# SCH_R2.net
KiCad netlist of a schematic drawn in EasyEDA
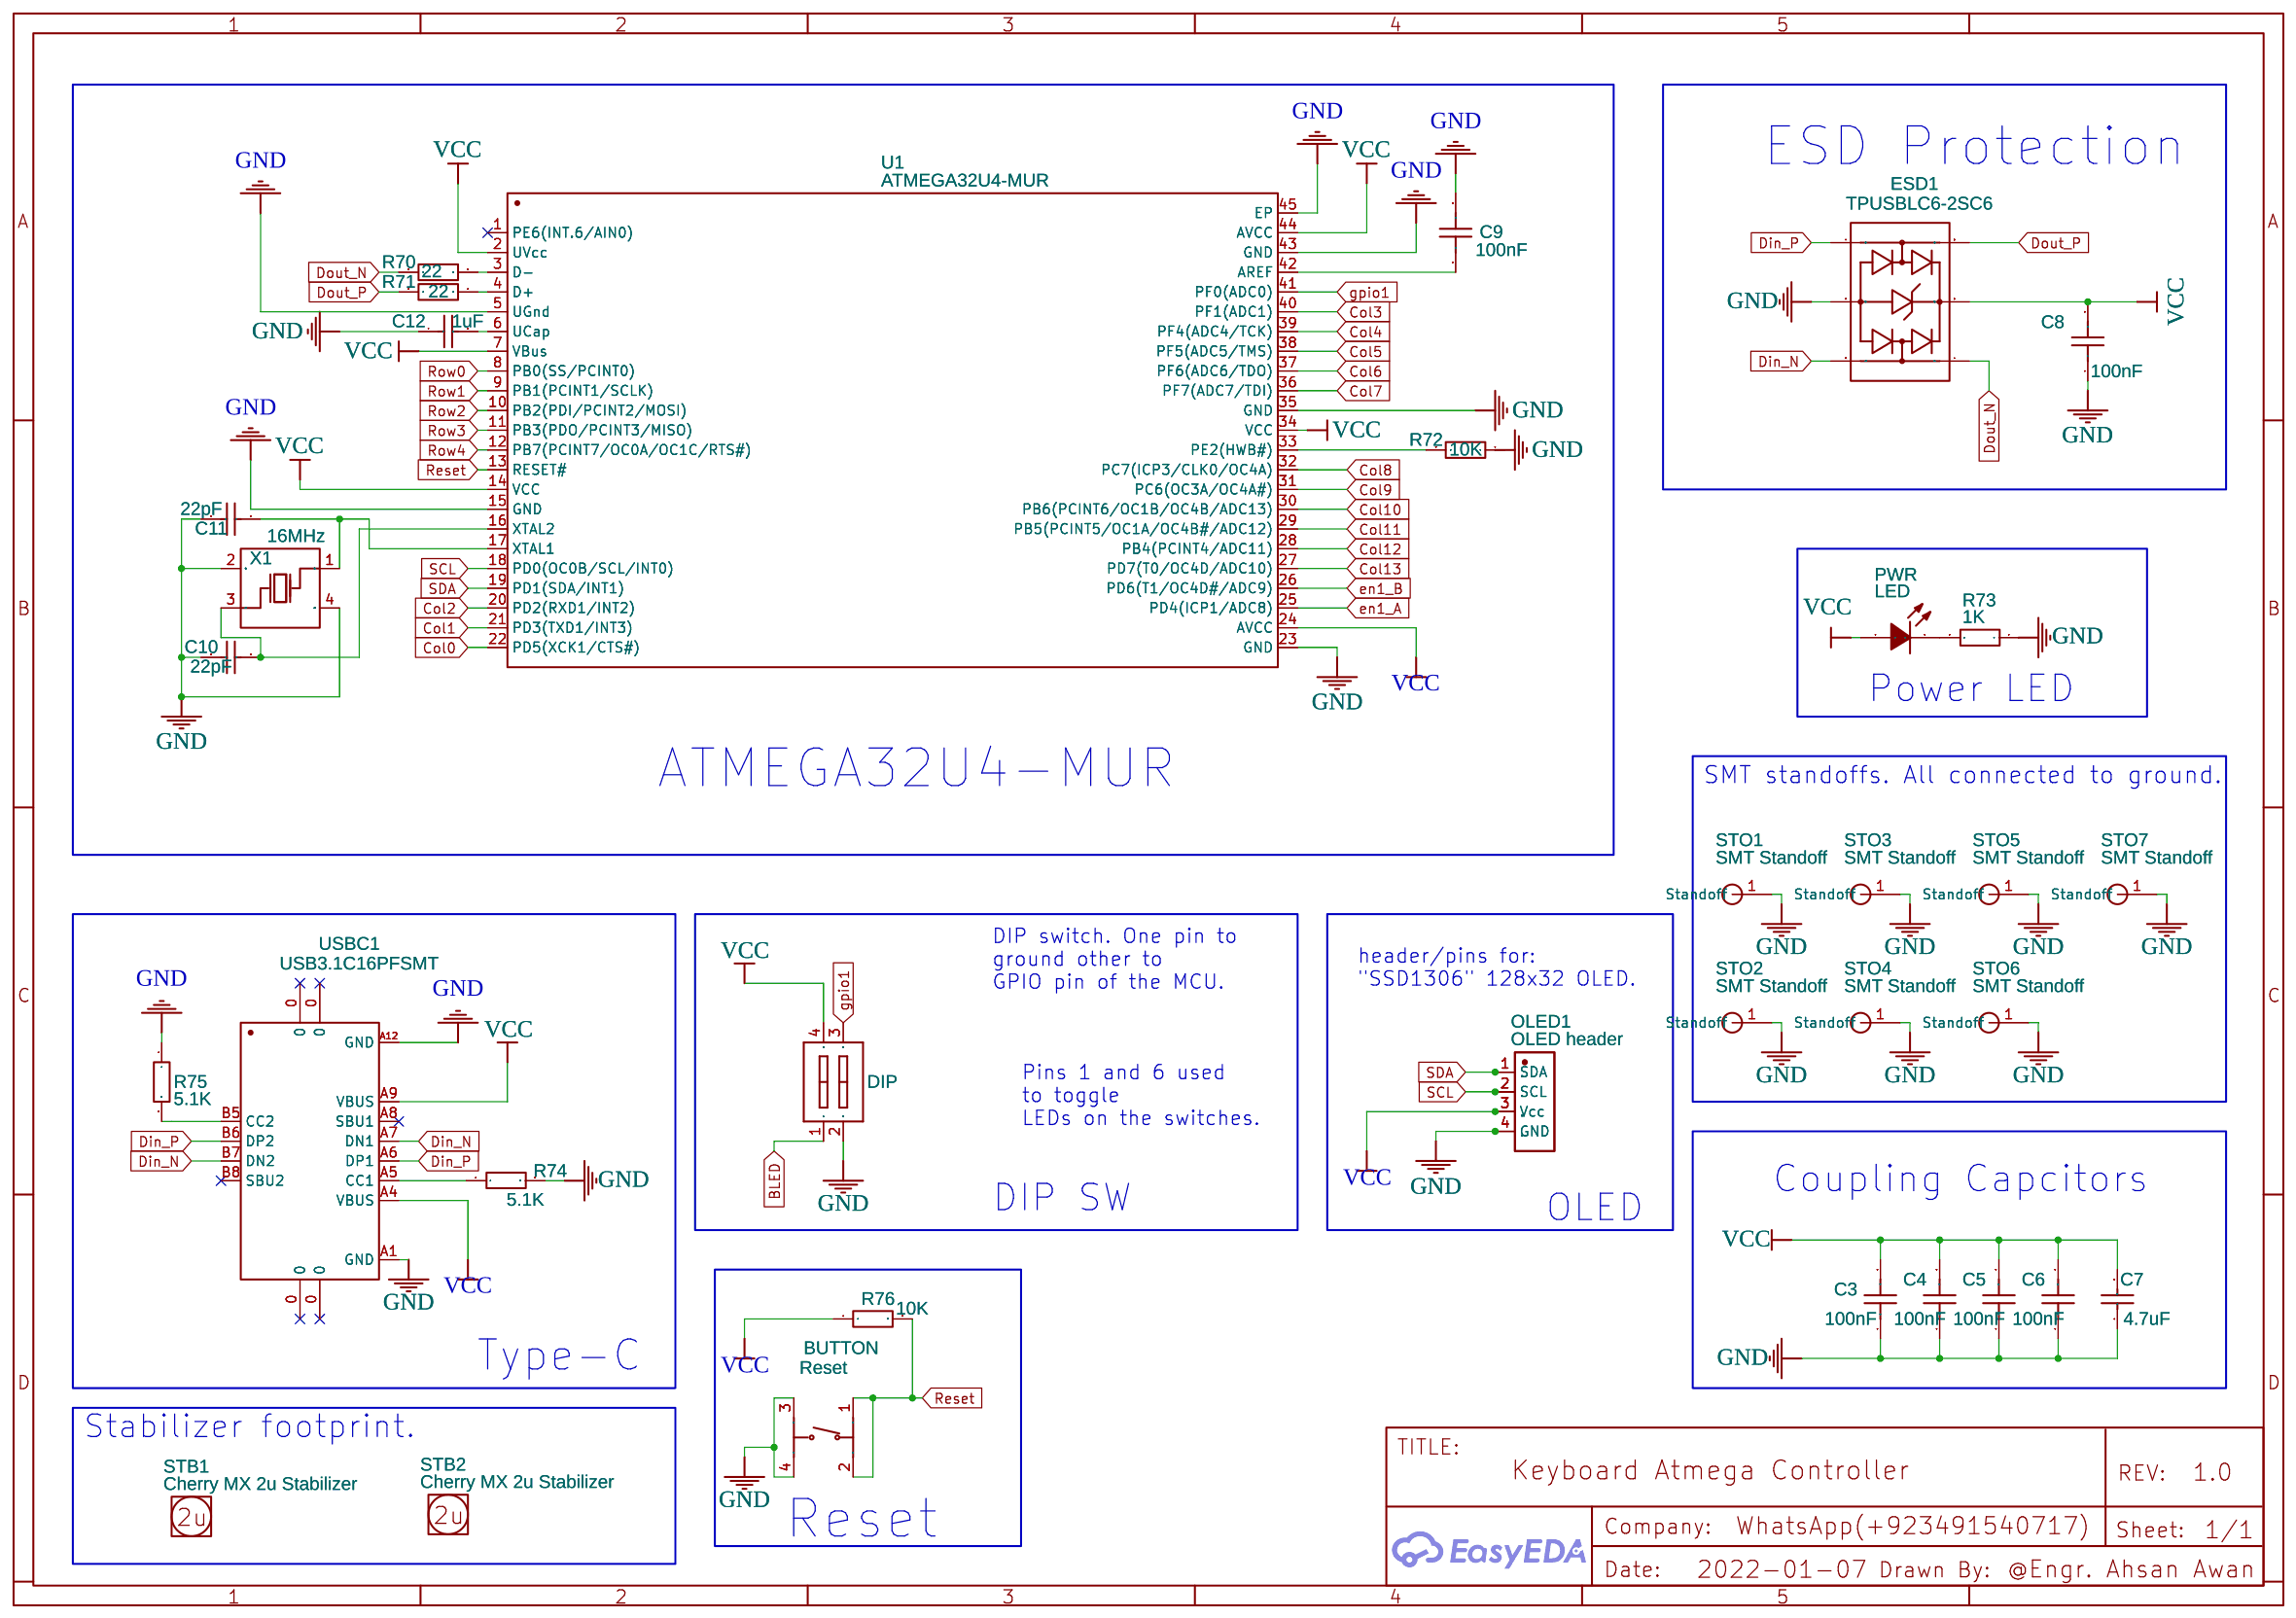
[diagram p0: Atmega MCU copy]
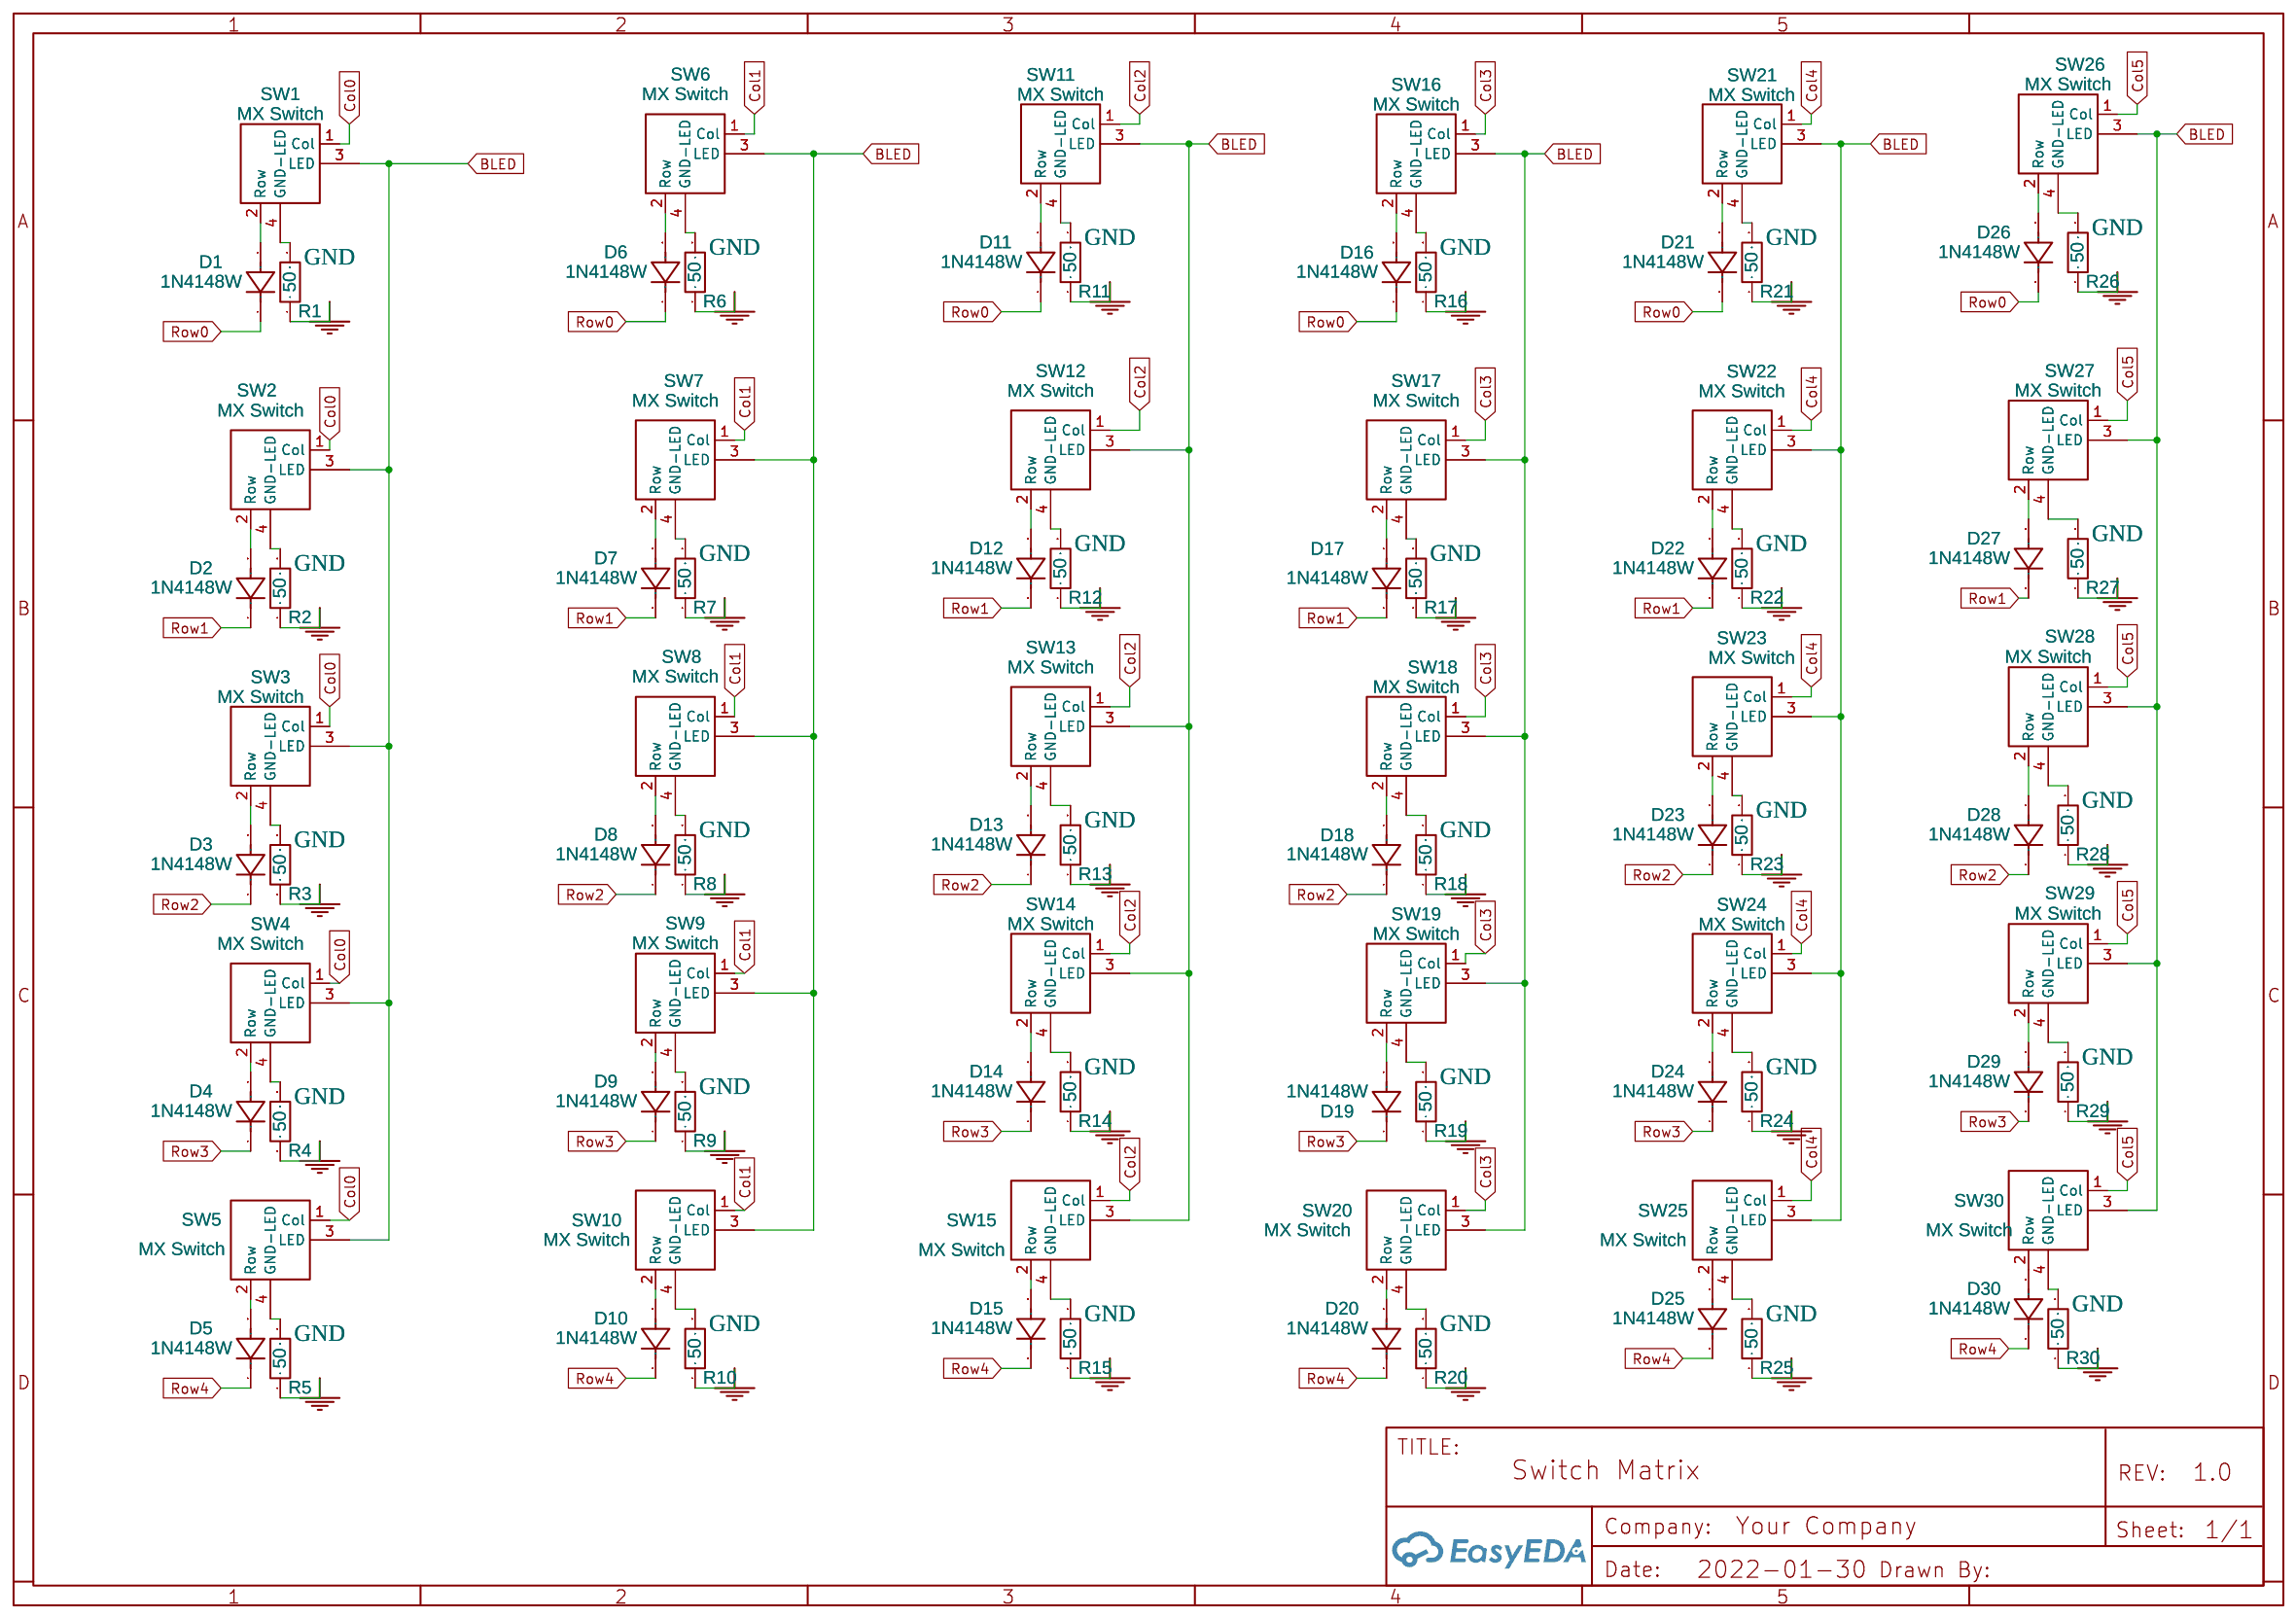
[diagram p1: First 6 Colimn]
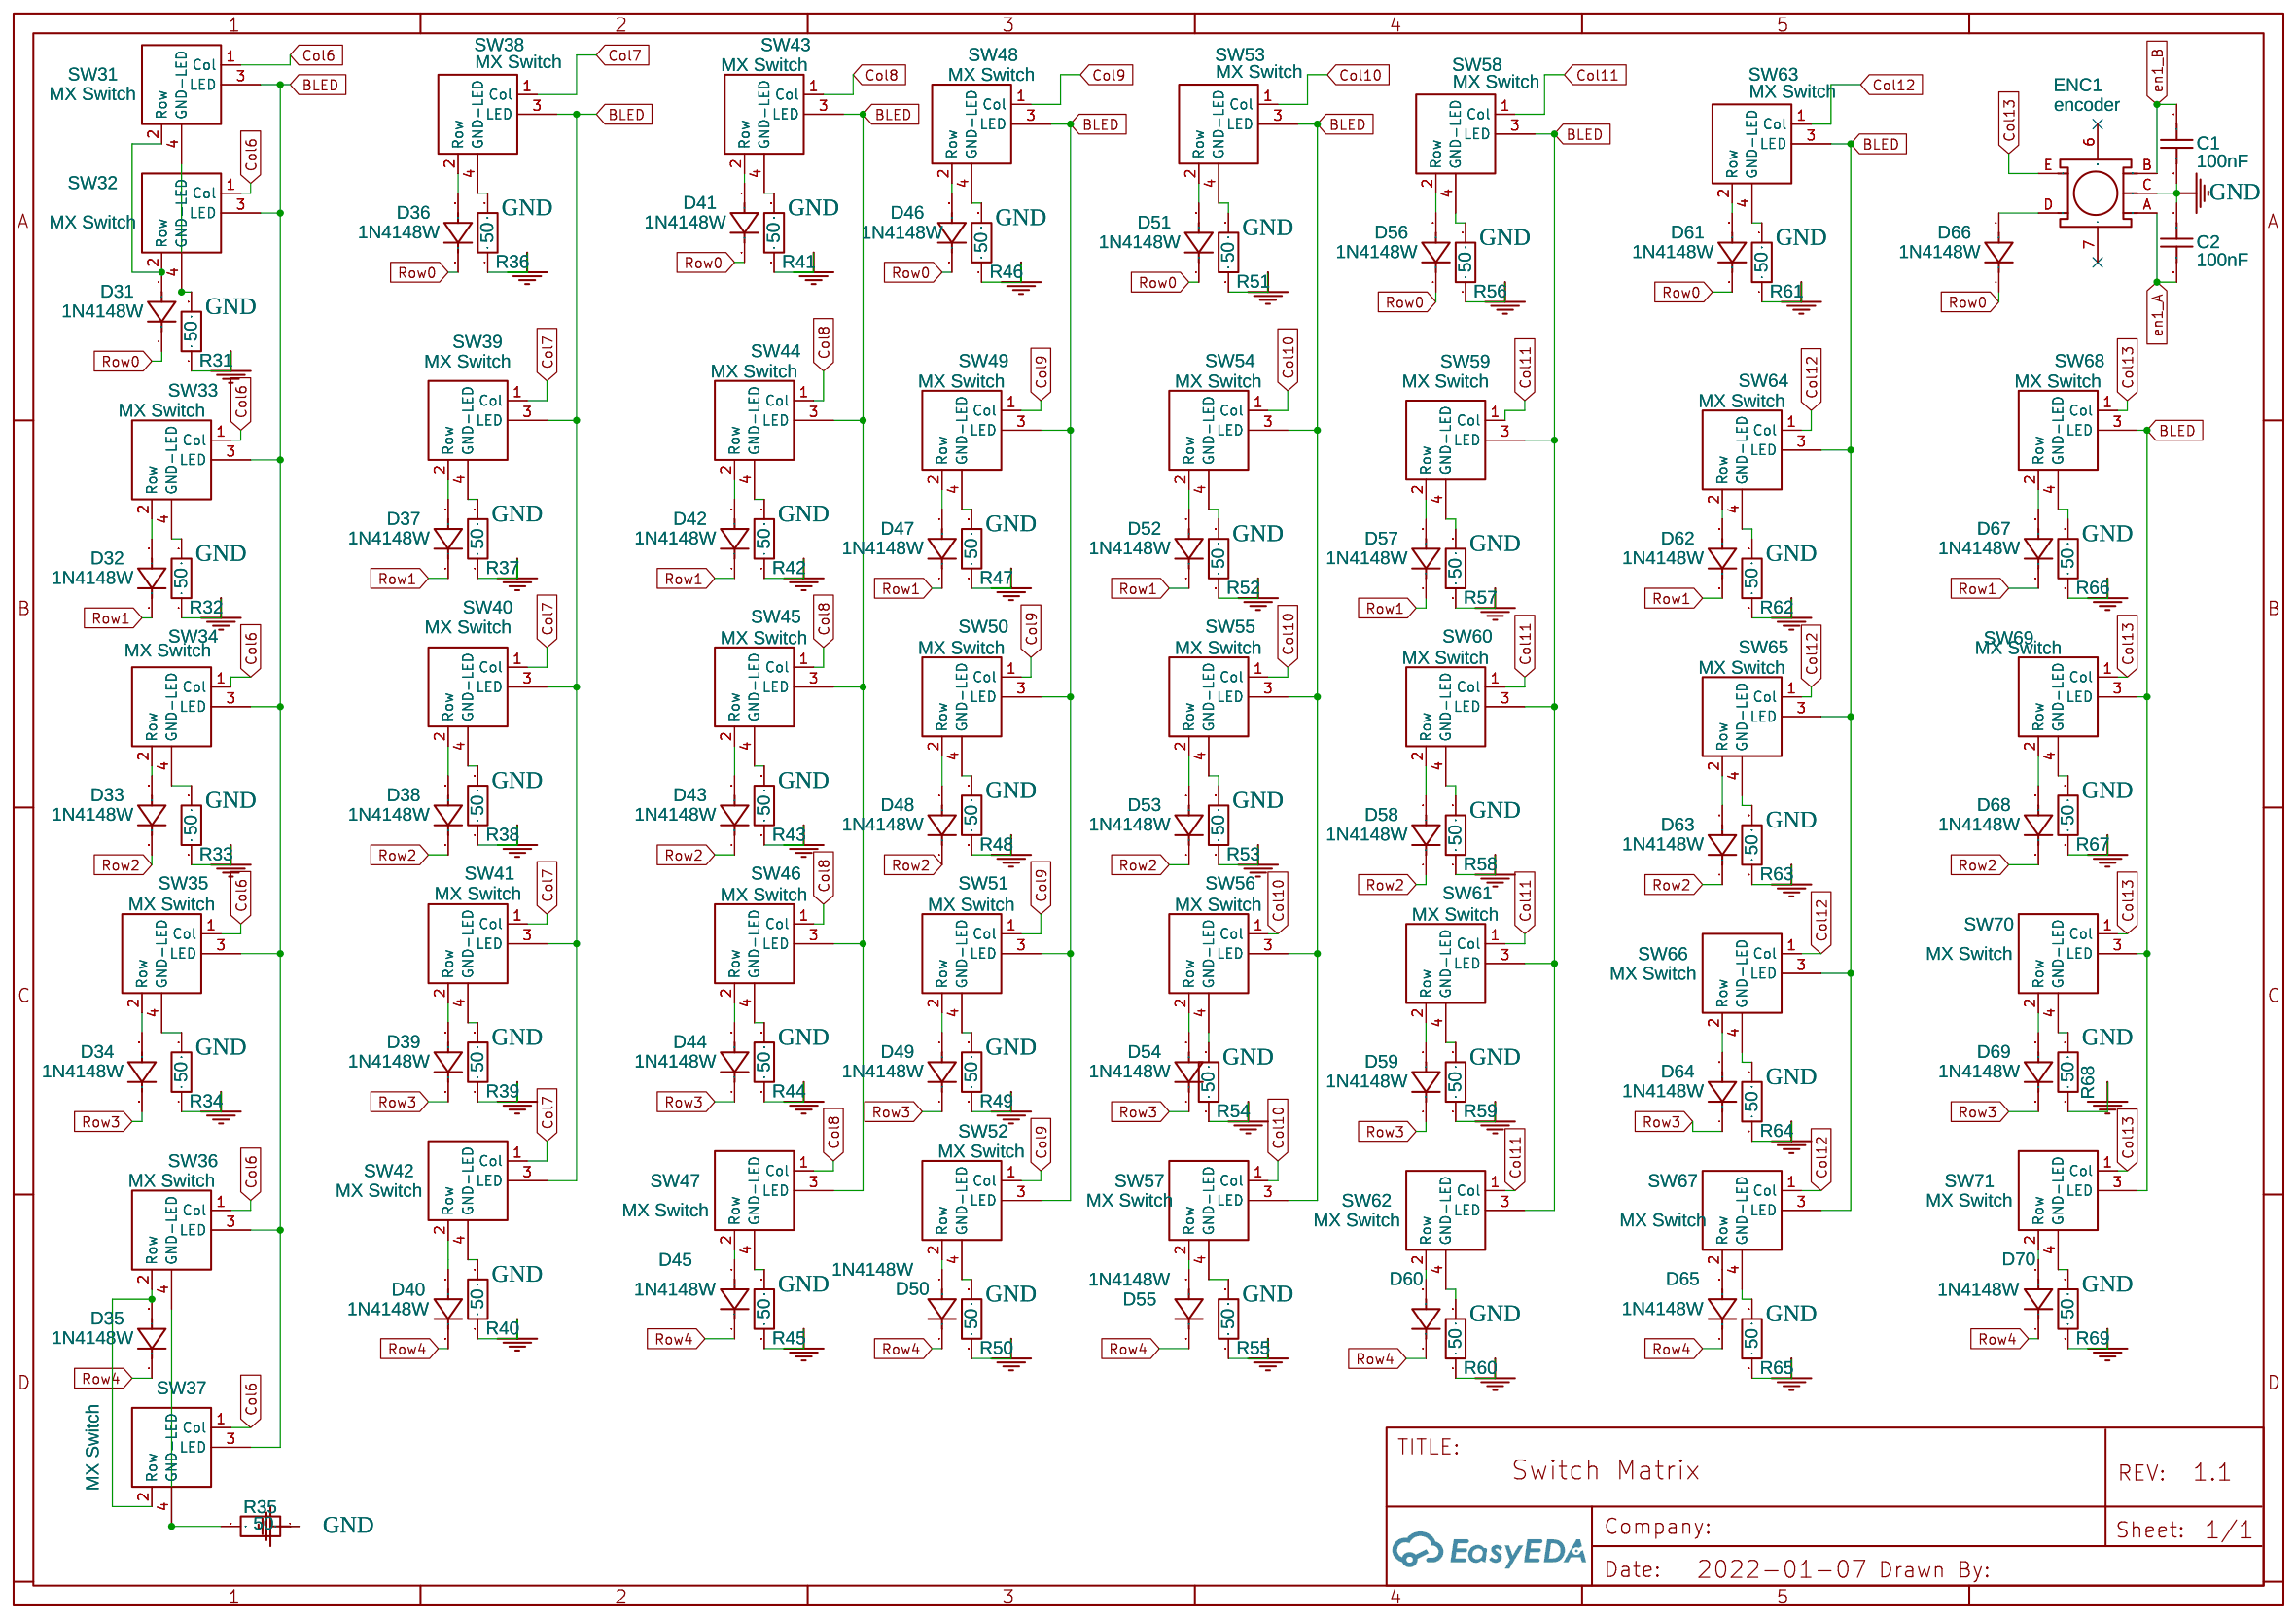
[diagram p2: Last 8 Col]

(export (version "E")
  (design (tool "Eeschema 10.0.6"))
  (components
    (comp (ref "BUTTON")
      (value "Reset")
      (fields
        (field (name "BOM_Manufacturer Part") "TS-1187A-B-A-B")
        (field (name "BOM_Supplier Part") "C318884")
      )
      (libsource (lib "") (part "TS-1187A-B-A-B"))
    )
    (comp (ref "C3")
      (value "100nF")
      (fields
        (field (name "BOM_Manufacturer Part") "CC0603KRX7R9BB104")
        (field (name "BOM_Supplier Part") "C14663")
      )
      (libsource (lib "") (part "CC0603KRX7R9BB104"))
    )
    (comp (ref "C4")
      (value "100nF")
      (fields
        (field (name "BOM_Manufacturer Part") "CC0603KRX7R9BB104")
        (field (name "BOM_Supplier Part") "C14663")
      )
      (libsource (lib "") (part "CC0603KRX7R9BB104"))
    )
    (comp (ref "C5")
      (value "100nF")
      (fields
        (field (name "BOM_Manufacturer Part") "CC0603KRX7R9BB104")
        (field (name "BOM_Supplier Part") "C14663")
      )
      (libsource (lib "") (part "CC0603KRX7R9BB104"))
    )
    (comp (ref "C6")
      (value "100nF")
      (fields
        (field (name "BOM_Manufacturer Part") "CC0603KRX7R9BB104")
        (field (name "BOM_Supplier Part") "C14663")
      )
      (libsource (lib "") (part "CC0603KRX7R9BB104"))
    )
    (comp (ref "C7")
      (value "4.7uF")
      (fields
        (field (name "BOM_Manufacturer Part") "CL10A475KO8NNNC")
        (field (name "BOM_Supplier Part") "C19666")
      )
      (libsource (lib "") (part "CL10A475KO8NNNC"))
    )
    (comp (ref "C8")
      (value "100nF")
      (fields
        (field (name "BOM_Manufacturer Part") "CC0603KRX7R9BB104")
        (field (name "BOM_Supplier Part") "C14663")
      )
      (libsource (lib "") (part "CC0603KRX7R9BB104"))
    )
    (comp (ref "C9")
      (value "100nF")
      (fields
        (field (name "BOM_Manufacturer Part") "CC0603KRX7R9BB104")
        (field (name "BOM_Supplier Part") "C14663")
      )
      (libsource (lib "") (part "CC0603KRX7R9BB104"))
    )
    (comp (ref "C10")
      (value "22pF")
      (fields
        (field (name "BOM_Manufacturer Part") "CL10C220JB8NNNC")
        (field (name "BOM_Supplier Part") "C1653")
      )
      (libsource (lib "") (part "CL10C220JB8NNNC"))
    )
    (comp (ref "C11")
      (value "22pF")
      (fields
        (field (name "BOM_Manufacturer Part") "CL10C220JB8NNNC")
        (field (name "BOM_Supplier Part") "C1653")
      )
      (libsource (lib "") (part "CL10C220JB8NNNC"))
    )
    (comp (ref "C12")
      (value "1uF")
      (fields
        (field (name "BOM_Manufacturer Part") "CL10A105KB8NNNC")
        (field (name "BOM_Supplier Part") "C15849")
      )
      (libsource (lib "") (part "CL10A105KB8NNNC"))
    )
    (comp (ref "DIP")
      (value "DSIC02LS-P_C489174")
      (fields
        (field (name "BOM_Manufacturer Part") "DSIC02LS-P")
        (field (name "BOM_Supplier Part") "C489174")
      )
      (libsource (lib "") (part "DSIC02LS-P_C489174"))
    )
    (comp (ref "ESD1")
      (value "TPUSBLC6-2SC6")
      (fields (field (name "BOM_Supplier Part") "C558442"))
      (libsource (lib "") (part "TPUSBLC6-2SC6"))
    )
    (comp (ref "OLED1")
      (value "OLED header")
      (fields
        (field (name "BOM_Manufacturer Part") "X4611WRS-04I-C40D28")
        (field (name "BOM_Supplier Part") "C917591")
      )
      (libsource (lib "") (part "X4611WRS-04I-C40D28"))
    )
    (comp (ref "PWR")
      (value "LED")
      (fields
        (field (name "BOM_Manufacturer Part") "TJ-S2012SW8TGLC6B-A5")
        (field (name "BOM_Supplier Part") "C192320")
      )
      (libsource (lib "") (part "TJ-S2012SW8TGLC6B-A5"))
    )
    (comp (ref "R70")
      (value "22")
      (fields
        (field (name "BOM_Manufacturer Part") "0603WAF220JT5E")
        (field (name "BOM_Supplier Part") "C23345")
      )
      (libsource (lib "") (part "0603WAF220JT5E"))
    )
    (comp (ref "R71")
      (value "22")
      (fields
        (field (name "BOM_Manufacturer Part") "0603WAF220JT5E")
        (field (name "BOM_Supplier Part") "C23345")
      )
      (libsource (lib "") (part "0603WAF220JT5E"))
    )
    (comp (ref "R72")
      (value "10K")
      (fields
        (field (name "BOM_Manufacturer Part") "0603WAF1002T5E")
        (field (name "BOM_Supplier Part") "C25804")
      )
      (libsource (lib "") (part "0603WAF1002T5E"))
    )
    (comp (ref "R73")
      (value "1K")
      (fields
        (field (name "BOM_Manufacturer Part") "TR0603B1KP0525")
        (field (name "BOM_Supplier Part") "C188364")
      )
      (libsource (lib "") (part "TR0603B1KP0525"))
    )
    (comp (ref "R74")
      (value "5.1K")
      (fields
        (field (name "BOM_Manufacturer Part") "RMC06035.1K1%N")
        (field (name "BOM_Supplier Part") "C269716")
      )
      (libsource (lib "") (part "RMC06035.1K1%N"))
    )
    (comp (ref "R75")
      (value "5.1K")
      (fields
        (field (name "BOM_Manufacturer Part") "RMC06035.1K1%N")
        (field (name "BOM_Supplier Part") "C269716")
      )
      (libsource (lib "") (part "RMC06035.1K1%N_1"))
    )
    (comp (ref "R76")
      (value "10K")
      (fields
        (field (name "BOM_Manufacturer Part") "0603WAF1002T5E")
        (field (name "BOM_Supplier Part") "C25804")
      )
      (libsource (lib "") (part "0603WAF1002T5E_1"))
    )
    (comp (ref "STB1")
      (value "Cherry MX 2u Stabilizer")
      (fields
        (field (name "BOM_Manufacturer Part") "G99-0742")
        (field (name "BOM_Supplier Part") "540-G99-0742")
      )
      (libsource (lib "") (part "Cherry MX 2u Stabilizer"))
    )
    (comp (ref "STB2")
      (value "Cherry MX 2u Stabilizer")
      (fields
        (field (name "BOM_Manufacturer Part") "G99-0742")
        (field (name "BOM_Supplier Part") "540-G99-0742")
      )
      (libsource (lib "") (part "Cherry MX 2u Stabilizer"))
    )
    (comp (ref "STO1")
      (value "SMT Standoff")
      (fields (field (name "BOM_Manufacturer Part") "9774040151R"))
      (libsource (lib "") (part "SMT Standoff"))
    )
    (comp (ref "STO2")
      (value "SMT Standoff")
      (fields (field (name "BOM_Manufacturer Part") "9774040151R"))
      (libsource (lib "") (part "SMT Standoff"))
    )
    (comp (ref "STO3")
      (value "SMT Standoff")
      (fields (field (name "BOM_Manufacturer Part") "9774040151R"))
      (libsource (lib "") (part "SMT Standoff"))
    )
    (comp (ref "STO4")
      (value "SMT Standoff")
      (fields (field (name "BOM_Manufacturer Part") "9774040151R"))
      (libsource (lib "") (part "SMT Standoff"))
    )
    (comp (ref "STO5")
      (value "SMT Standoff")
      (fields (field (name "BOM_Manufacturer Part") "9774040151R"))
      (libsource (lib "") (part "SMT Standoff"))
    )
    (comp (ref "STO6")
      (value "SMT Standoff")
      (fields (field (name "BOM_Manufacturer Part") "9774040151R"))
      (libsource (lib "") (part "SMT Standoff"))
    )
    (comp (ref "STO7")
      (value "SMT Standoff")
      (fields (field (name "BOM_Manufacturer Part") "9774040151R"))
      (libsource (lib "") (part "SMT Standoff"))
    )
    (comp (ref "U1")
      (value "ATMEGA32U4-MUR")
      (fields (field (name "BOM_Supplier Part") "C45874"))
      (libsource (lib "") (part "ATMEGA32U4-MUR"))
    )
    (comp (ref "U2")
      (value "x")
      (fields
        (field (name "BOM_Manufacturer Part") "PZ2.54-1X4P-ZW")
        (field (name "BOM_Supplier Part") "C2837836")
      )
      (libsource (lib "") (part "PZ2.54-1X4P-ZW"))
    )
    (comp (ref "USBC1")
      (value "USB3.1C16PFSMT")
      (fields (field (name "BOM_Supplier Part") "C167321"))
      (libsource (lib "") (part "USB3.1C16PFSMT"))
    )
    (comp (ref "X1")
      (value "16MHz")
      (fields
        (field (name "BOM_Manufacturer Part") "X322516MLB4SI")
        (field (name "BOM_Supplier Part") "C13738")
      )
      (libsource (lib "") (part "X322516MLB4SI"))
    )
    (comp (ref "D1")
      (value "1N4148W")
      (fields (field (name "BOM_Supplier Part") "C2828417"))
      (libsource (lib "") (part "1N4148W_C2828417"))
    )
    (comp (ref "D2")
      (value "1N4148W")
      (fields (field (name "BOM_Supplier Part") "C2828417"))
      (libsource (lib "") (part "1N4148W_C2828417"))
    )
    (comp (ref "D3")
      (value "1N4148W")
      (fields (field (name "BOM_Supplier Part") "C2828417"))
      (libsource (lib "") (part "1N4148W_C2828417"))
    )
    (comp (ref "D4")
      (value "1N4148W")
      (fields (field (name "BOM_Supplier Part") "C2828417"))
      (libsource (lib "") (part "1N4148W_C2828417"))
    )
    (comp (ref "D5")
      (value "1N4148W")
      (fields (field (name "BOM_Supplier Part") "C2828417"))
      (libsource (lib "") (part "1N4148W_C2828417"))
    )
    (comp (ref "D6")
      (value "1N4148W")
      (fields (field (name "BOM_Supplier Part") "C2828417"))
      (libsource (lib "") (part "1N4148W_C2828417"))
    )
    (comp (ref "D7")
      (value "1N4148W")
      (fields (field (name "BOM_Supplier Part") "C2828417"))
      (libsource (lib "") (part "1N4148W_C2828417"))
    )
    (comp (ref "D8")
      (value "1N4148W")
      (fields (field (name "BOM_Supplier Part") "C2828417"))
      (libsource (lib "") (part "1N4148W_C2828417"))
    )
    (comp (ref "D9")
      (value "1N4148W")
      (fields (field (name "BOM_Supplier Part") "C2828417"))
      (libsource (lib "") (part "1N4148W_C2828417"))
    )
    (comp (ref "D10")
      (value "1N4148W")
      (fields (field (name "BOM_Supplier Part") "C2828417"))
      (libsource (lib "") (part "1N4148W_C2828417"))
    )
    (comp (ref "D11")
      (value "1N4148W")
      (fields (field (name "BOM_Supplier Part") "C2828417"))
      (libsource (lib "") (part "1N4148W_C2828417"))
    )
    (comp (ref "D12")
      (value "1N4148W")
      (fields (field (name "BOM_Supplier Part") "C2828417"))
      (libsource (lib "") (part "1N4148W_C2828417"))
    )
    (comp (ref "D13")
      (value "1N4148W")
      (fields (field (name "BOM_Supplier Part") "C2828417"))
      (libsource (lib "") (part "1N4148W_C2828417"))
    )
    (comp (ref "D14")
      (value "1N4148W")
      (fields (field (name "BOM_Supplier Part") "C2828417"))
      (libsource (lib "") (part "1N4148W_C2828417"))
    )
    (comp (ref "D15")
      (value "1N4148W")
      (fields (field (name "BOM_Supplier Part") "C2828417"))
      (libsource (lib "") (part "1N4148W_C2828417"))
    )
    (comp (ref "D16")
      (value "1N4148W")
      (fields (field (name "BOM_Supplier Part") "C2828417"))
      (libsource (lib "") (part "1N4148W_C2828417"))
    )
    (comp (ref "D17")
      (value "1N4148W")
      (fields (field (name "BOM_Supplier Part") "C2828417"))
      (libsource (lib "") (part "1N4148W_C2828417"))
    )
    (comp (ref "D18")
      (value "1N4148W")
      (fields (field (name "BOM_Supplier Part") "C2828417"))
      (libsource (lib "") (part "1N4148W_C2828417"))
    )
    (comp (ref "D19")
      (value "1N4148W")
      (fields (field (name "BOM_Supplier Part") "C2828417"))
      (libsource (lib "") (part "1N4148W_C2828417"))
    )
    (comp (ref "D20")
      (value "1N4148W")
      (fields (field (name "BOM_Supplier Part") "C2828417"))
      (libsource (lib "") (part "1N4148W_C2828417"))
    )
    (comp (ref "D21")
      (value "1N4148W")
      (fields (field (name "BOM_Supplier Part") "C2828417"))
      (libsource (lib "") (part "1N4148W_C2828417"))
    )
    (comp (ref "D22")
      (value "1N4148W")
      (fields (field (name "BOM_Supplier Part") "C2828417"))
      (libsource (lib "") (part "1N4148W_C2828417"))
    )
    (comp (ref "D23")
      (value "1N4148W")
      (fields (field (name "BOM_Supplier Part") "C2828417"))
      (libsource (lib "") (part "1N4148W_C2828417"))
    )
    (comp (ref "D24")
      (value "1N4148W")
      (fields (field (name "BOM_Supplier Part") "C2828417"))
      (libsource (lib "") (part "1N4148W_C2828417"))
    )
    (comp (ref "D25")
      (value "1N4148W")
      (fields (field (name "BOM_Supplier Part") "C2828417"))
      (libsource (lib "") (part "1N4148W_C2828417"))
    )
    (comp (ref "D26")
      (value "1N4148W")
      (fields (field (name "BOM_Supplier Part") "C2828417"))
      (libsource (lib "") (part "1N4148W_C2828417"))
    )
    (comp (ref "D27")
      (value "1N4148W")
      (fields (field (name "BOM_Supplier Part") "C2828417"))
      (libsource (lib "") (part "1N4148W_C2828417"))
    )
    (comp (ref "D28")
      (value "1N4148W")
      (fields (field (name "BOM_Supplier Part") "C2828417"))
      (libsource (lib "") (part "1N4148W_C2828417"))
    )
    (comp (ref "D29")
      (value "1N4148W")
      (fields (field (name "BOM_Supplier Part") "C2828417"))
      (libsource (lib "") (part "1N4148W_C2828417"))
    )
    (comp (ref "D30")
      (value "1N4148W")
      (fields (field (name "BOM_Supplier Part") "C2828417"))
      (libsource (lib "") (part "1N4148W_C2828417"))
    )
    (comp (ref "R1")
      (value "50")
      (fields
        (field (name "BOM_Manufacturer Part") "HP03W5F500JT5E")
        (field (name "BOM_Supplier Part") "C2759402")
      )
      (libsource (lib "") (part "HP03W5F500JT5E"))
    )
    (comp (ref "R2")
      (value "50")
      (fields
        (field (name "BOM_Manufacturer Part") "HP03W5F500JT5E")
        (field (name "BOM_Supplier Part") "C2759402")
      )
      (libsource (lib "") (part "HP03W5F500JT5E"))
    )
    (comp (ref "R3")
      (value "50")
      (fields
        (field (name "BOM_Manufacturer Part") "HP03W5F500JT5E")
        (field (name "BOM_Supplier Part") "C2759402")
      )
      (libsource (lib "") (part "HP03W5F500JT5E"))
    )
    (comp (ref "R4")
      (value "50")
      (fields
        (field (name "BOM_Manufacturer Part") "HP03W5F500JT5E")
        (field (name "BOM_Supplier Part") "C2759402")
      )
      (libsource (lib "") (part "HP03W5F500JT5E"))
    )
    (comp (ref "R5")
      (value "50")
      (fields
        (field (name "BOM_Manufacturer Part") "HP03W5F500JT5E")
        (field (name "BOM_Supplier Part") "C2759402")
      )
      (libsource (lib "") (part "HP03W5F500JT5E"))
    )
    (comp (ref "R6")
      (value "50")
      (fields
        (field (name "BOM_Manufacturer Part") "HP03W5F500JT5E")
        (field (name "BOM_Supplier Part") "C2759402")
      )
      (libsource (lib "") (part "HP03W5F500JT5E"))
    )
    (comp (ref "R7")
      (value "50")
      (fields
        (field (name "BOM_Manufacturer Part") "HP03W5F500JT5E")
        (field (name "BOM_Supplier Part") "C2759402")
      )
      (libsource (lib "") (part "HP03W5F500JT5E"))
    )
    (comp (ref "R8")
      (value "50")
      (fields
        (field (name "BOM_Manufacturer Part") "HP03W5F500JT5E")
        (field (name "BOM_Supplier Part") "C2759402")
      )
      (libsource (lib "") (part "HP03W5F500JT5E"))
    )
    (comp (ref "R9")
      (value "50")
      (fields
        (field (name "BOM_Manufacturer Part") "HP03W5F500JT5E")
        (field (name "BOM_Supplier Part") "C2759402")
      )
      (libsource (lib "") (part "HP03W5F500JT5E"))
    )
    (comp (ref "R10")
      (value "50")
      (fields
        (field (name "BOM_Manufacturer Part") "HP03W5F500JT5E")
        (field (name "BOM_Supplier Part") "C2759402")
      )
      (libsource (lib "") (part "HP03W5F500JT5E"))
    )
    (comp (ref "R11")
      (value "50")
      (fields
        (field (name "BOM_Manufacturer Part") "HP03W5F500JT5E")
        (field (name "BOM_Supplier Part") "C2759402")
      )
      (libsource (lib "") (part "HP03W5F500JT5E"))
    )
    (comp (ref "R12")
      (value "50")
      (fields
        (field (name "BOM_Manufacturer Part") "HP03W5F500JT5E")
        (field (name "BOM_Supplier Part") "C2759402")
      )
      (libsource (lib "") (part "HP03W5F500JT5E"))
    )
    (comp (ref "R13")
      (value "50")
      (fields
        (field (name "BOM_Manufacturer Part") "HP03W5F500JT5E")
        (field (name "BOM_Supplier Part") "C2759402")
      )
      (libsource (lib "") (part "HP03W5F500JT5E"))
    )
    (comp (ref "R14")
      (value "50")
      (fields
        (field (name "BOM_Manufacturer Part") "HP03W5F500JT5E")
        (field (name "BOM_Supplier Part") "C2759402")
      )
      (libsource (lib "") (part "HP03W5F500JT5E"))
    )
    (comp (ref "R15")
      (value "50")
      (fields
        (field (name "BOM_Manufacturer Part") "HP03W5F500JT5E")
        (field (name "BOM_Supplier Part") "C2759402")
      )
      (libsource (lib "") (part "HP03W5F500JT5E"))
    )
    (comp (ref "R16")
      (value "50")
      (fields
        (field (name "BOM_Manufacturer Part") "HP03W5F500JT5E")
        (field (name "BOM_Supplier Part") "C2759402")
      )
      (libsource (lib "") (part "HP03W5F500JT5E"))
    )
    (comp (ref "R17")
      (value "50")
      (fields
        (field (name "BOM_Manufacturer Part") "HP03W5F500JT5E")
        (field (name "BOM_Supplier Part") "C2759402")
      )
      (libsource (lib "") (part "HP03W5F500JT5E"))
    )
    (comp (ref "R18")
      (value "50")
      (fields
        (field (name "BOM_Manufacturer Part") "HP03W5F500JT5E")
        (field (name "BOM_Supplier Part") "C2759402")
      )
      (libsource (lib "") (part "HP03W5F500JT5E"))
    )
    (comp (ref "R19")
      (value "50")
      (fields
        (field (name "BOM_Manufacturer Part") "HP03W5F500JT5E")
        (field (name "BOM_Supplier Part") "C2759402")
      )
      (libsource (lib "") (part "HP03W5F500JT5E"))
    )
    (comp (ref "R20")
      (value "50")
      (fields
        (field (name "BOM_Manufacturer Part") "HP03W5F500JT5E")
        (field (name "BOM_Supplier Part") "C2759402")
      )
      (libsource (lib "") (part "HP03W5F500JT5E"))
    )
    (comp (ref "R21")
      (value "50")
      (fields
        (field (name "BOM_Manufacturer Part") "HP03W5F500JT5E")
        (field (name "BOM_Supplier Part") "C2759402")
      )
      (libsource (lib "") (part "HP03W5F500JT5E"))
    )
    (comp (ref "R22")
      (value "50")
      (fields
        (field (name "BOM_Manufacturer Part") "HP03W5F500JT5E")
        (field (name "BOM_Supplier Part") "C2759402")
      )
      (libsource (lib "") (part "HP03W5F500JT5E"))
    )
    (comp (ref "R23")
      (value "50")
      (fields
        (field (name "BOM_Manufacturer Part") "HP03W5F500JT5E")
        (field (name "BOM_Supplier Part") "C2759402")
      )
      (libsource (lib "") (part "HP03W5F500JT5E"))
    )
    (comp (ref "R24")
      (value "50")
      (fields
        (field (name "BOM_Manufacturer Part") "HP03W5F500JT5E")
        (field (name "BOM_Supplier Part") "C2759402")
      )
      (libsource (lib "") (part "HP03W5F500JT5E"))
    )
    (comp (ref "R25")
      (value "50")
      (fields
        (field (name "BOM_Manufacturer Part") "HP03W5F500JT5E")
        (field (name "BOM_Supplier Part") "C2759402")
      )
      (libsource (lib "") (part "HP03W5F500JT5E"))
    )
    (comp (ref "R26")
      (value "50")
      (fields
        (field (name "BOM_Manufacturer Part") "HP03W5F500JT5E")
        (field (name "BOM_Supplier Part") "C2759402")
      )
      (libsource (lib "") (part "HP03W5F500JT5E"))
    )
    (comp (ref "R27")
      (value "50")
      (fields
        (field (name "BOM_Manufacturer Part") "HP03W5F500JT5E")
        (field (name "BOM_Supplier Part") "C2759402")
      )
      (libsource (lib "") (part "HP03W5F500JT5E"))
    )
    (comp (ref "R28")
      (value "50")
      (fields
        (field (name "BOM_Manufacturer Part") "HP03W5F500JT5E")
        (field (name "BOM_Supplier Part") "C2759402")
      )
      (libsource (lib "") (part "HP03W5F500JT5E"))
    )
    (comp (ref "R29")
      (value "50")
      (fields
        (field (name "BOM_Manufacturer Part") "HP03W5F500JT5E")
        (field (name "BOM_Supplier Part") "C2759402")
      )
      (libsource (lib "") (part "HP03W5F500JT5E"))
    )
    (comp (ref "R30")
      (value "50")
      (fields
        (field (name "BOM_Manufacturer Part") "HP03W5F500JT5E")
        (field (name "BOM_Supplier Part") "C2759402")
      )
      (libsource (lib "") (part "HP03W5F500JT5E"))
    )
    (comp (ref "SW1")
      (value "MX Switch")
      (fields (field (name "BOM_Supplier Part") "Cherry MX or Alps/Matias switch"))
      (libsource (lib "") (part "MX Switch"))
    )
    (comp (ref "SW2")
      (value "MX Switch")
      (fields (field (name "BOM_Supplier Part") "Cherry MX or Alps/Matias switch"))
      (libsource (lib "") (part "MX Switch"))
    )
    (comp (ref "SW3")
      (value "MX Switch")
      (fields (field (name "BOM_Supplier Part") "Cherry MX or Alps/Matias switch"))
      (libsource (lib "") (part "MX Switch"))
    )
    (comp (ref "SW4")
      (value "MX Switch")
      (fields (field (name "BOM_Supplier Part") "Cherry MX or Alps/Matias switch"))
      (libsource (lib "") (part "MX Switch"))
    )
    (comp (ref "SW5")
      (value "MX Switch")
      (fields (field (name "BOM_Supplier Part") "Cherry MX or Alps/Matias switch"))
      (libsource (lib "") (part "MX Switch"))
    )
    (comp (ref "SW6")
      (value "MX Switch")
      (fields (field (name "BOM_Supplier Part") "Cherry MX or Alps/Matias switch"))
      (libsource (lib "") (part "MX Switch"))
    )
    (comp (ref "SW7")
      (value "MX Switch")
      (fields (field (name "BOM_Supplier Part") "Cherry MX or Alps/Matias switch"))
      (libsource (lib "") (part "MX Switch"))
    )
    (comp (ref "SW8")
      (value "MX Switch")
      (fields (field (name "BOM_Supplier Part") "Cherry MX or Alps/Matias switch"))
      (libsource (lib "") (part "MX Switch"))
    )
    (comp (ref "SW9")
      (value "MX Switch")
      (fields (field (name "BOM_Supplier Part") "Cherry MX or Alps/Matias switch"))
      (libsource (lib "") (part "MX Switch"))
    )
    (comp (ref "SW10")
      (value "MX Switch")
      (fields (field (name "BOM_Supplier Part") "Cherry MX or Alps/Matias switch"))
      (libsource (lib "") (part "MX Switch"))
    )
    (comp (ref "SW11")
      (value "MX Switch")
      (fields (field (name "BOM_Supplier Part") "Cherry MX or Alps/Matias switch"))
      (libsource (lib "") (part "MX Switch"))
    )
    (comp (ref "SW12")
      (value "MX Switch")
      (fields (field (name "BOM_Supplier Part") "Cherry MX or Alps/Matias switch"))
      (libsource (lib "") (part "MX Switch"))
    )
    (comp (ref "SW13")
      (value "MX Switch")
      (fields (field (name "BOM_Supplier Part") "Cherry MX or Alps/Matias switch"))
      (libsource (lib "") (part "MX Switch"))
    )
    (comp (ref "SW14")
      (value "MX Switch")
      (fields (field (name "BOM_Supplier Part") "Cherry MX or Alps/Matias switch"))
      (libsource (lib "") (part "MX Switch"))
    )
    (comp (ref "SW15")
      (value "MX Switch")
      (fields (field (name "BOM_Supplier Part") "Cherry MX or Alps/Matias switch"))
      (libsource (lib "") (part "MX Switch"))
    )
    (comp (ref "SW16")
      (value "MX Switch")
      (fields (field (name "BOM_Supplier Part") "Cherry MX or Alps/Matias switch"))
      (libsource (lib "") (part "MX Switch"))
    )
    (comp (ref "SW17")
      (value "MX Switch")
      (fields (field (name "BOM_Supplier Part") "Cherry MX or Alps/Matias switch"))
      (libsource (lib "") (part "MX Switch"))
    )
    (comp (ref "SW18")
      (value "MX Switch")
      (fields (field (name "BOM_Supplier Part") "Cherry MX or Alps/Matias switch"))
      (libsource (lib "") (part "MX Switch"))
    )
    (comp (ref "SW19")
      (value "MX Switch")
      (fields (field (name "BOM_Supplier Part") "Cherry MX or Alps/Matias switch"))
      (libsource (lib "") (part "MX Switch"))
    )
    (comp (ref "SW20")
      (value "MX Switch")
      (fields (field (name "BOM_Supplier Part") "Cherry MX or Alps/Matias switch"))
      (libsource (lib "") (part "MX Switch"))
    )
    (comp (ref "SW21")
      (value "MX Switch")
      (fields (field (name "BOM_Supplier Part") "Cherry MX or Alps/Matias switch"))
      (libsource (lib "") (part "MX Switch"))
    )
    (comp (ref "SW22")
      (value "MX Switch")
      (fields (field (name "BOM_Supplier Part") "Cherry MX or Alps/Matias switch"))
      (libsource (lib "") (part "MX Switch"))
    )
    (comp (ref "SW23")
      (value "MX Switch")
      (fields (field (name "BOM_Supplier Part") "Cherry MX or Alps/Matias switch"))
      (libsource (lib "") (part "MX Switch"))
    )
    (comp (ref "SW24")
      (value "MX Switch")
      (fields (field (name "BOM_Supplier Part") "Cherry MX or Alps/Matias switch"))
      (libsource (lib "") (part "MX Switch"))
    )
    (comp (ref "SW25")
      (value "MX Switch")
      (fields (field (name "BOM_Supplier Part") "Cherry MX or Alps/Matias switch"))
      (libsource (lib "") (part "MX Switch"))
    )
    (comp (ref "SW26")
      (value "MX Switch")
      (fields (field (name "BOM_Supplier Part") "Cherry MX or Alps/Matias switch"))
      (libsource (lib "") (part "MX Switch"))
    )
    (comp (ref "SW27")
      (value "MX Switch")
      (fields (field (name "BOM_Supplier Part") "Cherry MX or Alps/Matias switch"))
      (libsource (lib "") (part "MX Switch"))
    )
    (comp (ref "SW28")
      (value "MX Switch")
      (fields (field (name "BOM_Supplier Part") "Cherry MX or Alps/Matias switch"))
      (libsource (lib "") (part "MX Switch"))
    )
    (comp (ref "SW29")
      (value "MX Switch")
      (fields (field (name "BOM_Supplier Part") "Cherry MX or Alps/Matias switch"))
      (libsource (lib "") (part "MX Switch"))
    )
    (comp (ref "SW30")
      (value "MX Switch")
      (fields (field (name "BOM_Supplier Part") "Cherry MX or Alps/Matias switch"))
      (libsource (lib "") (part "MX Switch"))
    )
    (comp (ref "C1")
      (value "100nF")
      (fields
        (field (name "BOM_Manufacturer Part") "CC0603KRX7R9BB104")
        (field (name "BOM_Supplier Part") "C14663")
      )
      (libsource (lib "") (part "CC0603KRX7R9BB104"))
    )
    (comp (ref "C2")
      (value "100nF")
      (fields
        (field (name "BOM_Manufacturer Part") "CC0603KRX7R9BB104")
        (field (name "BOM_Supplier Part") "C14663")
      )
      (libsource (lib "") (part "CC0603KRX7R9BB104"))
    )
    (comp (ref "D31")
      (value "1N4148W")
      (fields (field (name "BOM_Supplier Part") "C2828417"))
      (libsource (lib "") (part "1N4148W_C2828417"))
    )
    (comp (ref "D32")
      (value "1N4148W")
      (fields (field (name "BOM_Supplier Part") "C2828417"))
      (libsource (lib "") (part "1N4148W_C2828417"))
    )
    (comp (ref "D33")
      (value "1N4148W")
      (fields (field (name "BOM_Supplier Part") "C2828417"))
      (libsource (lib "") (part "1N4148W_C2828417"))
    )
    (comp (ref "D34")
      (value "1N4148W")
      (fields (field (name "BOM_Supplier Part") "C2828417"))
      (libsource (lib "") (part "1N4148W_C2828417"))
    )
    (comp (ref "D35")
      (value "1N4148W")
      (fields (field (name "BOM_Supplier Part") "C2828417"))
      (libsource (lib "") (part "1N4148W_C2828417"))
    )
    (comp (ref "D36")
      (value "1N4148W")
      (fields (field (name "BOM_Supplier Part") "C2828417"))
      (libsource (lib "") (part "1N4148W_C2828417"))
    )
    (comp (ref "D37")
      (value "1N4148W")
      (fields (field (name "BOM_Supplier Part") "C2828417"))
      (libsource (lib "") (part "1N4148W_C2828417"))
    )
    (comp (ref "D38")
      (value "1N4148W")
      (fields (field (name "BOM_Supplier Part") "C2828417"))
      (libsource (lib "") (part "1N4148W_C2828417"))
    )
    (comp (ref "D39")
      (value "1N4148W")
      (fields (field (name "BOM_Supplier Part") "C2828417"))
      (libsource (lib "") (part "1N4148W_C2828417"))
    )
    (comp (ref "D40")
      (value "1N4148W")
      (fields (field (name "BOM_Supplier Part") "C2828417"))
      (libsource (lib "") (part "1N4148W_C2828417"))
    )
    (comp (ref "D41")
      (value "1N4148W")
      (fields (field (name "BOM_Supplier Part") "C2828417"))
      (libsource (lib "") (part "1N4148W_C2828417"))
    )
    (comp (ref "D42")
      (value "1N4148W")
      (fields (field (name "BOM_Supplier Part") "C2828417"))
      (libsource (lib "") (part "1N4148W_C2828417"))
    )
    (comp (ref "D43")
      (value "1N4148W")
      (fields (field (name "BOM_Supplier Part") "C2828417"))
      (libsource (lib "") (part "1N4148W_C2828417"))
    )
    (comp (ref "D44")
      (value "1N4148W")
      (fields (field (name "BOM_Supplier Part") "C2828417"))
      (libsource (lib "") (part "1N4148W_C2828417"))
    )
    (comp (ref "D45")
      (value "1N4148W")
      (fields (field (name "BOM_Supplier Part") "C2828417"))
      (libsource (lib "") (part "1N4148W_C2828417"))
    )
    (comp (ref "D46")
      (value "1N4148W")
      (fields (field (name "BOM_Supplier Part") "C2828417"))
      (libsource (lib "") (part "1N4148W_C2828417"))
    )
    (comp (ref "D47")
      (value "1N4148W")
      (fields (field (name "BOM_Supplier Part") "C2828417"))
      (libsource (lib "") (part "1N4148W_C2828417"))
    )
    (comp (ref "D48")
      (value "1N4148W")
      (fields (field (name "BOM_Supplier Part") "C2828417"))
      (libsource (lib "") (part "1N4148W_C2828417"))
    )
    (comp (ref "D49")
      (value "1N4148W")
      (fields (field (name "BOM_Supplier Part") "C2828417"))
      (libsource (lib "") (part "1N4148W_C2828417"))
    )
    (comp (ref "D50")
      (value "1N4148W")
      (fields (field (name "BOM_Supplier Part") "C2828417"))
      (libsource (lib "") (part "1N4148W_C2828417"))
    )
    (comp (ref "D51")
      (value "1N4148W")
      (fields (field (name "BOM_Supplier Part") "C2828417"))
      (libsource (lib "") (part "1N4148W_C2828417"))
    )
    (comp (ref "D52")
      (value "1N4148W")
      (fields (field (name "BOM_Supplier Part") "C2828417"))
      (libsource (lib "") (part "1N4148W_C2828417"))
    )
    (comp (ref "D53")
      (value "1N4148W")
      (fields (field (name "BOM_Supplier Part") "C2828417"))
      (libsource (lib "") (part "1N4148W_C2828417"))
    )
    (comp (ref "D54")
      (value "1N4148W")
      (fields (field (name "BOM_Supplier Part") "C2828417"))
      (libsource (lib "") (part "1N4148W_C2828417"))
    )
    (comp (ref "D55")
      (value "1N4148W")
      (fields (field (name "BOM_Supplier Part") "C2828417"))
      (libsource (lib "") (part "1N4148W_C2828417"))
    )
    (comp (ref "D56")
      (value "1N4148W")
      (fields (field (name "BOM_Supplier Part") "C2828417"))
      (libsource (lib "") (part "1N4148W_C2828417"))
    )
    (comp (ref "D57")
      (value "1N4148W")
      (fields (field (name "BOM_Supplier Part") "C2828417"))
      (libsource (lib "") (part "1N4148W_C2828417"))
    )
    (comp (ref "D58")
      (value "1N4148W")
      (fields (field (name "BOM_Supplier Part") "C2828417"))
      (libsource (lib "") (part "1N4148W_C2828417"))
    )
    (comp (ref "D59")
      (value "1N4148W")
      (fields (field (name "BOM_Supplier Part") "C2828417"))
      (libsource (lib "") (part "1N4148W_C2828417"))
    )
    (comp (ref "D60")
      (value "1N4148W")
      (fields (field (name "BOM_Supplier Part") "C2828417"))
      (libsource (lib "") (part "1N4148W_C2828417"))
    )
    (comp (ref "D61")
      (value "1N4148W")
      (fields (field (name "BOM_Supplier Part") "C2828417"))
      (libsource (lib "") (part "1N4148W_C2828417"))
    )
    (comp (ref "D62")
      (value "1N4148W")
      (fields (field (name "BOM_Supplier Part") "C2828417"))
      (libsource (lib "") (part "1N4148W_C2828417"))
    )
    (comp (ref "D63")
      (value "1N4148W")
      (fields (field (name "BOM_Supplier Part") "C2828417"))
      (libsource (lib "") (part "1N4148W_C2828417"))
    )
    (comp (ref "D64")
      (value "1N4148W")
      (fields (field (name "BOM_Supplier Part") "C2828417"))
      (libsource (lib "") (part "1N4148W_C2828417"))
    )
    (comp (ref "D65")
      (value "1N4148W")
      (fields (field (name "BOM_Supplier Part") "C2828417"))
      (libsource (lib "") (part "1N4148W_C2828417"))
    )
    (comp (ref "D66")
      (value "1N4148W")
      (fields (field (name "BOM_Supplier Part") "C2828417"))
      (libsource (lib "") (part "1N4148W_C2828417"))
    )
    (comp (ref "D67")
      (value "1N4148W")
      (fields (field (name "BOM_Supplier Part") "C2828417"))
      (libsource (lib "") (part "1N4148W_C2828417"))
    )
    (comp (ref "D68")
      (value "1N4148W")
      (fields (field (name "BOM_Supplier Part") "C2828417"))
      (libsource (lib "") (part "1N4148W_C2828417"))
    )
    (comp (ref "D69")
      (value "1N4148W")
      (fields (field (name "BOM_Supplier Part") "C2828417"))
      (libsource (lib "") (part "1N4148W_C2828417"))
    )
    (comp (ref "D70")
      (value "1N4148W")
      (fields (field (name "BOM_Supplier Part") "C2828417"))
      (libsource (lib "") (part "1N4148W_C2828417"))
    )
    (comp (ref "ENC1")
      (value "encoder")
      (fields
        (field (name "BOM_Manufacturer Part") "EC11E18244AU")
        (field (name "BOM_Supplier Part") "C202365")
      )
      (libsource (lib "") (part "EC11E18244AU"))
    )
    (comp (ref "R31")
      (value "50")
      (fields
        (field (name "BOM_Manufacturer Part") "HP03W5F500JT5E")
        (field (name "BOM_Supplier Part") "C2759402")
      )
      (libsource (lib "") (part "HP03W5F500JT5E"))
    )
    (comp (ref "R32")
      (value "50")
      (fields
        (field (name "BOM_Manufacturer Part") "HP03W5F500JT5E")
        (field (name "BOM_Supplier Part") "C2759402")
      )
      (libsource (lib "") (part "HP03W5F500JT5E"))
    )
    (comp (ref "R33")
      (value "50")
      (fields
        (field (name "BOM_Manufacturer Part") "HP03W5F500JT5E")
        (field (name "BOM_Supplier Part") "C2759402")
      )
      (libsource (lib "") (part "HP03W5F500JT5E"))
    )
    (comp (ref "R34")
      (value "50")
      (fields
        (field (name "BOM_Manufacturer Part") "HP03W5F500JT5E")
        (field (name "BOM_Supplier Part") "C2759402")
      )
      (libsource (lib "") (part "HP03W5F500JT5E"))
    )
    (comp (ref "R35")
      (value "50")
      (fields
        (field (name "BOM_Manufacturer Part") "HP03W5F500JT5E")
        (field (name "BOM_Supplier Part") "C2759402")
      )
      (libsource (lib "") (part "HP03W5F500JT5E_1"))
    )
    (comp (ref "R36")
      (value "50")
      (fields
        (field (name "BOM_Manufacturer Part") "HP03W5F500JT5E")
        (field (name "BOM_Supplier Part") "C2759402")
      )
      (libsource (lib "") (part "HP03W5F500JT5E"))
    )
    (comp (ref "R37")
      (value "50")
      (fields
        (field (name "BOM_Manufacturer Part") "HP03W5F500JT5E")
        (field (name "BOM_Supplier Part") "C2759402")
      )
      (libsource (lib "") (part "HP03W5F500JT5E"))
    )
    (comp (ref "R38")
      (value "50")
      (fields
        (field (name "BOM_Manufacturer Part") "HP03W5F500JT5E")
        (field (name "BOM_Supplier Part") "C2759402")
      )
      (libsource (lib "") (part "HP03W5F500JT5E"))
    )
    (comp (ref "R39")
      (value "50")
      (fields
        (field (name "BOM_Manufacturer Part") "HP03W5F500JT5E")
        (field (name "BOM_Supplier Part") "C2759402")
      )
      (libsource (lib "") (part "HP03W5F500JT5E"))
    )
    (comp (ref "R40")
      (value "50")
      (fields
        (field (name "BOM_Manufacturer Part") "HP03W5F500JT5E")
        (field (name "BOM_Supplier Part") "C2759402")
      )
      (libsource (lib "") (part "HP03W5F500JT5E"))
    )
    (comp (ref "R41")
      (value "50")
      (fields
        (field (name "BOM_Manufacturer Part") "HP03W5F500JT5E")
        (field (name "BOM_Supplier Part") "C2759402")
      )
      (libsource (lib "") (part "HP03W5F500JT5E"))
    )
    (comp (ref "R42")
      (value "50")
      (fields
        (field (name "BOM_Manufacturer Part") "HP03W5F500JT5E")
        (field (name "BOM_Supplier Part") "C2759402")
      )
      (libsource (lib "") (part "HP03W5F500JT5E"))
    )
    (comp (ref "R43")
      (value "50")
      (fields
        (field (name "BOM_Manufacturer Part") "HP03W5F500JT5E")
        (field (name "BOM_Supplier Part") "C2759402")
      )
      (libsource (lib "") (part "HP03W5F500JT5E"))
    )
    (comp (ref "R44")
      (value "50")
      (fields
        (field (name "BOM_Manufacturer Part") "HP03W5F500JT5E")
        (field (name "BOM_Supplier Part") "C2759402")
      )
      (libsource (lib "") (part "HP03W5F500JT5E"))
    )
    (comp (ref "R45")
      (value "50")
      (fields
        (field (name "BOM_Manufacturer Part") "HP03W5F500JT5E")
        (field (name "BOM_Supplier Part") "C2759402")
      )
      (libsource (lib "") (part "HP03W5F500JT5E"))
    )
    (comp (ref "R46")
      (value "50")
      (fields
        (field (name "BOM_Manufacturer Part") "HP03W5F500JT5E")
        (field (name "BOM_Supplier Part") "C2759402")
      )
      (libsource (lib "") (part "HP03W5F500JT5E"))
    )
    (comp (ref "R47")
      (value "50")
      (fields
        (field (name "BOM_Manufacturer Part") "HP03W5F500JT5E")
        (field (name "BOM_Supplier Part") "C2759402")
      )
      (libsource (lib "") (part "HP03W5F500JT5E"))
    )
    (comp (ref "R48")
      (value "50")
      (fields
        (field (name "BOM_Manufacturer Part") "HP03W5F500JT5E")
        (field (name "BOM_Supplier Part") "C2759402")
      )
      (libsource (lib "") (part "HP03W5F500JT5E"))
    )
    (comp (ref "R49")
      (value "50")
      (fields
        (field (name "BOM_Manufacturer Part") "HP03W5F500JT5E")
        (field (name "BOM_Supplier Part") "C2759402")
      )
      (libsource (lib "") (part "HP03W5F500JT5E"))
    )
    (comp (ref "R50")
      (value "50")
      (fields
        (field (name "BOM_Manufacturer Part") "HP03W5F500JT5E")
        (field (name "BOM_Supplier Part") "C2759402")
      )
      (libsource (lib "") (part "HP03W5F500JT5E"))
    )
    (comp (ref "R51")
      (value "50")
      (fields
        (field (name "BOM_Manufacturer Part") "HP03W5F500JT5E")
        (field (name "BOM_Supplier Part") "C2759402")
      )
      (libsource (lib "") (part "HP03W5F500JT5E"))
    )
    (comp (ref "R52")
      (value "50")
      (fields
        (field (name "BOM_Manufacturer Part") "HP03W5F500JT5E")
        (field (name "BOM_Supplier Part") "C2759402")
      )
      (libsource (lib "") (part "HP03W5F500JT5E"))
    )
    (comp (ref "R53")
      (value "50")
      (fields
        (field (name "BOM_Manufacturer Part") "HP03W5F500JT5E")
        (field (name "BOM_Supplier Part") "C2759402")
      )
      (libsource (lib "") (part "HP03W5F500JT5E"))
    )
    (comp (ref "R54")
      (value "50")
      (fields
        (field (name "BOM_Manufacturer Part") "HP03W5F500JT5E")
        (field (name "BOM_Supplier Part") "C2759402")
      )
      (libsource (lib "") (part "HP03W5F500JT5E"))
    )
    (comp (ref "R55")
      (value "50")
      (fields
        (field (name "BOM_Manufacturer Part") "HP03W5F500JT5E")
        (field (name "BOM_Supplier Part") "C2759402")
      )
      (libsource (lib "") (part "HP03W5F500JT5E"))
    )
    (comp (ref "R56")
      (value "50")
      (fields
        (field (name "BOM_Manufacturer Part") "HP03W5F500JT5E")
        (field (name "BOM_Supplier Part") "C2759402")
      )
      (libsource (lib "") (part "HP03W5F500JT5E"))
    )
    (comp (ref "R57")
      (value "50")
      (fields
        (field (name "BOM_Manufacturer Part") "HP03W5F500JT5E")
        (field (name "BOM_Supplier Part") "C2759402")
      )
      (libsource (lib "") (part "HP03W5F500JT5E"))
    )
    (comp (ref "R58")
      (value "50")
      (fields
        (field (name "BOM_Manufacturer Part") "HP03W5F500JT5E")
        (field (name "BOM_Supplier Part") "C2759402")
      )
      (libsource (lib "") (part "HP03W5F500JT5E"))
    )
    (comp (ref "R59")
      (value "50")
      (fields
        (field (name "BOM_Manufacturer Part") "HP03W5F500JT5E")
        (field (name "BOM_Supplier Part") "C2759402")
      )
      (libsource (lib "") (part "HP03W5F500JT5E"))
    )
    (comp (ref "R60")
      (value "50")
      (fields
        (field (name "BOM_Manufacturer Part") "HP03W5F500JT5E")
        (field (name "BOM_Supplier Part") "C2759402")
      )
      (libsource (lib "") (part "HP03W5F500JT5E"))
    )
    (comp (ref "R61")
      (value "50")
      (fields
        (field (name "BOM_Manufacturer Part") "HP03W5F500JT5E")
        (field (name "BOM_Supplier Part") "C2759402")
      )
      (libsource (lib "") (part "HP03W5F500JT5E"))
    )
    (comp (ref "R62")
      (value "50")
      (fields
        (field (name "BOM_Manufacturer Part") "HP03W5F500JT5E")
        (field (name "BOM_Supplier Part") "C2759402")
      )
      (libsource (lib "") (part "HP03W5F500JT5E"))
    )
    (comp (ref "R63")
      (value "50")
      (fields
        (field (name "BOM_Manufacturer Part") "HP03W5F500JT5E")
        (field (name "BOM_Supplier Part") "C2759402")
      )
      (libsource (lib "") (part "HP03W5F500JT5E"))
    )
    (comp (ref "R64")
      (value "50")
      (fields
        (field (name "BOM_Manufacturer Part") "HP03W5F500JT5E")
        (field (name "BOM_Supplier Part") "C2759402")
      )
      (libsource (lib "") (part "HP03W5F500JT5E"))
    )
    (comp (ref "R65")
      (value "50")
      (fields
        (field (name "BOM_Manufacturer Part") "HP03W5F500JT5E")
        (field (name "BOM_Supplier Part") "C2759402")
      )
      (libsource (lib "") (part "HP03W5F500JT5E"))
    )
    (comp (ref "R66")
      (value "50")
      (fields
        (field (name "BOM_Manufacturer Part") "HP03W5F500JT5E")
        (field (name "BOM_Supplier Part") "C2759402")
      )
      (libsource (lib "") (part "HP03W5F500JT5E"))
    )
    (comp (ref "R67")
      (value "50")
      (fields
        (field (name "BOM_Manufacturer Part") "HP03W5F500JT5E")
        (field (name "BOM_Supplier Part") "C2759402")
      )
      (libsource (lib "") (part "HP03W5F500JT5E"))
    )
    (comp (ref "R68")
      (value "50")
      (fields
        (field (name "BOM_Manufacturer Part") "HP03W5F500JT5E")
        (field (name "BOM_Supplier Part") "C2759402")
      )
      (libsource (lib "") (part "HP03W5F500JT5E"))
    )
    (comp (ref "R69")
      (value "50")
      (fields
        (field (name "BOM_Manufacturer Part") "HP03W5F500JT5E")
        (field (name "BOM_Supplier Part") "C2759402")
      )
      (libsource (lib "") (part "HP03W5F500JT5E"))
    )
    (comp (ref "SW31")
      (value "MX Switch")
      (fields (field (name "BOM_Supplier Part") "Cherry MX or Alps/Matias switch"))
      (libsource (lib "") (part "MX Switch"))
    )
    (comp (ref "SW32")
      (value "MX Switch")
      (fields (field (name "BOM_Supplier Part") "Cherry MX or Alps/Matias switch"))
      (libsource (lib "") (part "MX Switch"))
    )
    (comp (ref "SW33")
      (value "MX Switch")
      (fields (field (name "BOM_Supplier Part") "Cherry MX or Alps/Matias switch"))
      (libsource (lib "") (part "MX Switch"))
    )
    (comp (ref "SW34")
      (value "MX Switch")
      (fields (field (name "BOM_Supplier Part") "Cherry MX or Alps/Matias switch"))
      (libsource (lib "") (part "MX Switch"))
    )
    (comp (ref "SW35")
      (value "MX Switch")
      (fields (field (name "BOM_Supplier Part") "Cherry MX or Alps/Matias switch"))
      (libsource (lib "") (part "MX Switch"))
    )
    (comp (ref "SW36")
      (value "MX Switch")
      (fields (field (name "BOM_Supplier Part") "Cherry MX or Alps/Matias switch"))
      (libsource (lib "") (part "MX Switch"))
    )
    (comp (ref "SW37")
      (value "MX Switch")
      (fields (field (name "BOM_Supplier Part") "Cherry MX or Alps/Matias switch"))
      (libsource (lib "") (part "MX Switch"))
    )
    (comp (ref "SW38")
      (value "MX Switch")
      (fields (field (name "BOM_Supplier Part") "Cherry MX or Alps/Matias switch"))
      (libsource (lib "") (part "MX Switch"))
    )
    (comp (ref "SW39")
      (value "MX Switch")
      (fields (field (name "BOM_Supplier Part") "Cherry MX or Alps/Matias switch"))
      (libsource (lib "") (part "MX Switch"))
    )
    (comp (ref "SW40")
      (value "MX Switch")
      (fields (field (name "BOM_Supplier Part") "Cherry MX or Alps/Matias switch"))
      (libsource (lib "") (part "MX Switch"))
    )
    (comp (ref "SW41")
      (value "MX Switch")
      (fields (field (name "BOM_Supplier Part") "Cherry MX or Alps/Matias switch"))
      (libsource (lib "") (part "MX Switch"))
    )
    (comp (ref "SW42")
      (value "MX Switch")
      (fields (field (name "BOM_Supplier Part") "Cherry MX or Alps/Matias switch"))
      (libsource (lib "") (part "MX Switch"))
    )
    (comp (ref "SW43")
      (value "MX Switch")
      (fields (field (name "BOM_Supplier Part") "Cherry MX or Alps/Matias switch"))
      (libsource (lib "") (part "MX Switch"))
    )
    (comp (ref "SW44")
      (value "MX Switch")
      (fields (field (name "BOM_Supplier Part") "Cherry MX or Alps/Matias switch"))
      (libsource (lib "") (part "MX Switch"))
    )
    (comp (ref "SW45")
      (value "MX Switch")
      (fields (field (name "BOM_Supplier Part") "Cherry MX or Alps/Matias switch"))
      (libsource (lib "") (part "MX Switch"))
    )
    (comp (ref "SW46")
      (value "MX Switch")
      (fields (field (name "BOM_Supplier Part") "Cherry MX or Alps/Matias switch"))
      (libsource (lib "") (part "MX Switch"))
    )
    (comp (ref "SW47")
      (value "MX Switch")
      (fields (field (name "BOM_Supplier Part") "Cherry MX or Alps/Matias switch"))
      (libsource (lib "") (part "MX Switch"))
    )
    (comp (ref "SW48")
      (value "MX Switch")
      (fields (field (name "BOM_Supplier Part") "Cherry MX or Alps/Matias switch"))
      (libsource (lib "") (part "MX Switch"))
    )
    (comp (ref "SW49")
      (value "MX Switch")
      (fields (field (name "BOM_Supplier Part") "Cherry MX or Alps/Matias switch"))
      (libsource (lib "") (part "MX Switch"))
    )
    (comp (ref "SW50")
      (value "MX Switch")
      (fields (field (name "BOM_Supplier Part") "Cherry MX or Alps/Matias switch"))
      (libsource (lib "") (part "MX Switch"))
    )
    (comp (ref "SW51")
      (value "MX Switch")
      (fields (field (name "BOM_Supplier Part") "Cherry MX or Alps/Matias switch"))
      (libsource (lib "") (part "MX Switch"))
    )
    (comp (ref "SW52")
      (value "MX Switch")
      (fields (field (name "BOM_Supplier Part") "Cherry MX or Alps/Matias switch"))
      (libsource (lib "") (part "MX Switch"))
    )
    (comp (ref "SW53")
      (value "MX Switch")
      (fields (field (name "BOM_Supplier Part") "Cherry MX or Alps/Matias switch"))
      (libsource (lib "") (part "MX Switch"))
    )
    (comp (ref "SW54")
      (value "MX Switch")
      (fields (field (name "BOM_Supplier Part") "Cherry MX or Alps/Matias switch"))
      (libsource (lib "") (part "MX Switch"))
    )
    (comp (ref "SW55")
      (value "MX Switch")
      (fields (field (name "BOM_Supplier Part") "Cherry MX or Alps/Matias switch"))
      (libsource (lib "") (part "MX Switch"))
    )
    (comp (ref "SW56")
      (value "MX Switch")
      (fields (field (name "BOM_Supplier Part") "Cherry MX or Alps/Matias switch"))
      (libsource (lib "") (part "MX Switch"))
    )
    (comp (ref "SW57")
      (value "MX Switch")
      (fields (field (name "BOM_Supplier Part") "Cherry MX or Alps/Matias switch"))
      (libsource (lib "") (part "MX Switch"))
    )
    (comp (ref "SW58")
      (value "MX Switch")
      (fields (field (name "BOM_Supplier Part") "Cherry MX or Alps/Matias switch"))
      (libsource (lib "") (part "MX Switch"))
    )
    (comp (ref "SW59")
      (value "MX Switch")
      (fields (field (name "BOM_Supplier Part") "Cherry MX or Alps/Matias switch"))
      (libsource (lib "") (part "MX Switch"))
    )
    (comp (ref "SW60")
      (value "MX Switch")
      (fields (field (name "BOM_Supplier Part") "Cherry MX or Alps/Matias switch"))
      (libsource (lib "") (part "MX Switch"))
    )
    (comp (ref "SW61")
      (value "MX Switch")
      (fields (field (name "BOM_Supplier Part") "Cherry MX or Alps/Matias switch"))
      (libsource (lib "") (part "MX Switch"))
    )
    (comp (ref "SW62")
      (value "MX Switch")
      (fields (field (name "BOM_Supplier Part") "Cherry MX or Alps/Matias switch"))
      (libsource (lib "") (part "MX Switch"))
    )
    (comp (ref "SW63")
      (value "MX Switch")
      (fields (field (name "BOM_Supplier Part") "Cherry MX or Alps/Matias switch"))
      (libsource (lib "") (part "MX Switch"))
    )
    (comp (ref "SW64")
      (value "MX Switch")
      (fields (field (name "BOM_Supplier Part") "Cherry MX or Alps/Matias switch"))
      (libsource (lib "") (part "MX Switch"))
    )
    (comp (ref "SW65")
      (value "MX Switch")
      (fields (field (name "BOM_Supplier Part") "Cherry MX or Alps/Matias switch"))
      (libsource (lib "") (part "MX Switch"))
    )
    (comp (ref "SW66")
      (value "MX Switch")
      (fields (field (name "BOM_Supplier Part") "Cherry MX or Alps/Matias switch"))
      (libsource (lib "") (part "MX Switch"))
    )
    (comp (ref "SW67")
      (value "MX Switch")
      (fields (field (name "BOM_Supplier Part") "Cherry MX or Alps/Matias switch"))
      (libsource (lib "") (part "MX Switch"))
    )
    (comp (ref "SW68")
      (value "MX Switch")
      (fields (field (name "BOM_Supplier Part") "Cherry MX or Alps/Matias switch"))
      (libsource (lib "") (part "MX Switch"))
    )
    (comp (ref "SW69")
      (value "MX Switch")
      (fields (field (name "BOM_Supplier Part") "Cherry MX or Alps/Matias switch"))
      (libsource (lib "") (part "MX Switch"))
    )
    (comp (ref "SW70")
      (value "MX Switch")
      (fields (field (name "BOM_Supplier Part") "Cherry MX or Alps/Matias switch"))
      (libsource (lib "") (part "MX Switch"))
    )
    (comp (ref "SW71")
      (value "MX Switch")
      (fields (field (name "BOM_Supplier Part") "Cherry MX or Alps/Matias switch"))
      (libsource (lib "") (part "MX Switch"))
    )
  )
  (nets
    (net (code "1") (name "BLED") (class "Default")
      (node (ref "DIP") (pin "1") (pinfunction "A1_1") (pintype "input"))
      (node (ref "SW1") (pin "3") (pinfunction "LED_3") (pintype "unspecified"))
      (node (ref "SW10") (pin "3") (pinfunction "LED_3") (pintype "unspecified"))
      (node (ref "SW11") (pin "3") (pinfunction "LED_3") (pintype "unspecified"))
      (node (ref "SW12") (pin "3") (pinfunction "LED_3") (pintype "unspecified"))
      (node (ref "SW13") (pin "3") (pinfunction "LED_3") (pintype "unspecified"))
      (node (ref "SW14") (pin "3") (pinfunction "LED_3") (pintype "unspecified"))
      (node (ref "SW15") (pin "3") (pinfunction "LED_3") (pintype "unspecified"))
      (node (ref "SW16") (pin "3") (pinfunction "LED_3") (pintype "unspecified"))
      (node (ref "SW17") (pin "3") (pinfunction "LED_3") (pintype "unspecified"))
      (node (ref "SW18") (pin "3") (pinfunction "LED_3") (pintype "unspecified"))
      (node (ref "SW19") (pin "3") (pinfunction "LED_3") (pintype "unspecified"))
      (node (ref "SW2") (pin "3") (pinfunction "LED_3") (pintype "unspecified"))
      (node (ref "SW20") (pin "3") (pinfunction "LED_3") (pintype "unspecified"))
      (node (ref "SW21") (pin "3") (pinfunction "LED_3") (pintype "unspecified"))
      (node (ref "SW22") (pin "3") (pinfunction "LED_3") (pintype "unspecified"))
      (node (ref "SW23") (pin "3") (pinfunction "LED_3") (pintype "unspecified"))
      (node (ref "SW24") (pin "3") (pinfunction "LED_3") (pintype "unspecified"))
      (node (ref "SW25") (pin "3") (pinfunction "LED_3") (pintype "unspecified"))
      (node (ref "SW26") (pin "3") (pinfunction "LED_3") (pintype "unspecified"))
      (node (ref "SW27") (pin "3") (pinfunction "LED_3") (pintype "unspecified"))
      (node (ref "SW28") (pin "3") (pinfunction "LED_3") (pintype "unspecified"))
      (node (ref "SW29") (pin "3") (pinfunction "LED_3") (pintype "unspecified"))
      (node (ref "SW3") (pin "3") (pinfunction "LED_3") (pintype "unspecified"))
      (node (ref "SW30") (pin "3") (pinfunction "LED_3") (pintype "unspecified"))
      (node (ref "SW31") (pin "3") (pinfunction "LED_3") (pintype "unspecified"))
      (node (ref "SW32") (pin "3") (pinfunction "LED_3") (pintype "unspecified"))
      (node (ref "SW33") (pin "3") (pinfunction "LED_3") (pintype "unspecified"))
      (node (ref "SW34") (pin "3") (pinfunction "LED_3") (pintype "unspecified"))
      (node (ref "SW35") (pin "3") (pinfunction "LED_3") (pintype "unspecified"))
      (node (ref "SW36") (pin "3") (pinfunction "LED_3") (pintype "unspecified"))
      (node (ref "SW37") (pin "3") (pinfunction "LED_3") (pintype "unspecified"))
      (node (ref "SW38") (pin "3") (pinfunction "LED_3") (pintype "unspecified"))
      (node (ref "SW39") (pin "3") (pinfunction "LED_3") (pintype "unspecified"))
      (node (ref "SW4") (pin "3") (pinfunction "LED_3") (pintype "unspecified"))
      (node (ref "SW40") (pin "3") (pinfunction "LED_3") (pintype "unspecified"))
      (node (ref "SW41") (pin "3") (pinfunction "LED_3") (pintype "unspecified"))
      (node (ref "SW42") (pin "3") (pinfunction "LED_3") (pintype "unspecified"))
      (node (ref "SW43") (pin "3") (pinfunction "LED_3") (pintype "unspecified"))
      (node (ref "SW44") (pin "3") (pinfunction "LED_3") (pintype "unspecified"))
      (node (ref "SW45") (pin "3") (pinfunction "LED_3") (pintype "unspecified"))
      (node (ref "SW46") (pin "3") (pinfunction "LED_3") (pintype "unspecified"))
      (node (ref "SW47") (pin "3") (pinfunction "LED_3") (pintype "unspecified"))
      (node (ref "SW48") (pin "3") (pinfunction "LED_3") (pintype "unspecified"))
      (node (ref "SW49") (pin "3") (pinfunction "LED_3") (pintype "unspecified"))
      (node (ref "SW5") (pin "3") (pinfunction "LED_3") (pintype "unspecified"))
      (node (ref "SW50") (pin "3") (pinfunction "LED_3") (pintype "unspecified"))
      (node (ref "SW51") (pin "3") (pinfunction "LED_3") (pintype "unspecified"))
      (node (ref "SW52") (pin "3") (pinfunction "LED_3") (pintype "unspecified"))
      (node (ref "SW53") (pin "3") (pinfunction "LED_3") (pintype "unspecified"))
      (node (ref "SW54") (pin "3") (pinfunction "LED_3") (pintype "unspecified"))
      (node (ref "SW55") (pin "3") (pinfunction "LED_3") (pintype "unspecified"))
      (node (ref "SW56") (pin "3") (pinfunction "LED_3") (pintype "unspecified"))
      (node (ref "SW57") (pin "3") (pinfunction "LED_3") (pintype "unspecified"))
      (node (ref "SW58") (pin "3") (pinfunction "LED_3") (pintype "unspecified"))
      (node (ref "SW59") (pin "3") (pinfunction "LED_3") (pintype "unspecified"))
      (node (ref "SW6") (pin "3") (pinfunction "LED_3") (pintype "unspecified"))
      (node (ref "SW60") (pin "3") (pinfunction "LED_3") (pintype "unspecified"))
      (node (ref "SW61") (pin "3") (pinfunction "LED_3") (pintype "unspecified"))
      (node (ref "SW62") (pin "3") (pinfunction "LED_3") (pintype "unspecified"))
      (node (ref "SW63") (pin "3") (pinfunction "LED_3") (pintype "unspecified"))
      (node (ref "SW64") (pin "3") (pinfunction "LED_3") (pintype "unspecified"))
      (node (ref "SW65") (pin "3") (pinfunction "LED_3") (pintype "unspecified"))
      (node (ref "SW66") (pin "3") (pinfunction "LED_3") (pintype "unspecified"))
      (node (ref "SW67") (pin "3") (pinfunction "LED_3") (pintype "unspecified"))
      (node (ref "SW68") (pin "3") (pinfunction "LED_3") (pintype "unspecified"))
      (node (ref "SW69") (pin "3") (pinfunction "LED_3") (pintype "unspecified"))
      (node (ref "SW7") (pin "3") (pinfunction "LED_3") (pintype "unspecified"))
      (node (ref "SW70") (pin "3") (pinfunction "LED_3") (pintype "unspecified"))
      (node (ref "SW71") (pin "3") (pinfunction "LED_3") (pintype "unspecified"))
      (node (ref "SW8") (pin "3") (pinfunction "LED_3") (pintype "unspecified"))
      (node (ref "SW9") (pin "3") (pinfunction "LED_3") (pintype "unspecified"))
    )
    (net (code "2") (name "Col0") (class "Default")
      (node (ref "SW1") (pin "1") (pinfunction "Col_1") (pintype "unspecified"))
      (node (ref "SW2") (pin "1") (pinfunction "Col_1") (pintype "unspecified"))
      (node (ref "SW3") (pin "1") (pinfunction "Col_1") (pintype "unspecified"))
      (node (ref "SW4") (pin "1") (pinfunction "Col_1") (pintype "unspecified"))
      (node (ref "SW5") (pin "1") (pinfunction "Col_1") (pintype "unspecified"))
      (node (ref "U1") (pin "22") (pinfunction "PD5(XCK1/CTS#)_22") (pintype "unspecified"))
    )
    (net (code "3") (name "Col1") (class "Default")
      (node (ref "SW10") (pin "1") (pinfunction "Col_1") (pintype "unspecified"))
      (node (ref "SW6") (pin "1") (pinfunction "Col_1") (pintype "unspecified"))
      (node (ref "SW7") (pin "1") (pinfunction "Col_1") (pintype "unspecified"))
      (node (ref "SW8") (pin "1") (pinfunction "Col_1") (pintype "unspecified"))
      (node (ref "SW9") (pin "1") (pinfunction "Col_1") (pintype "unspecified"))
      (node (ref "U1") (pin "21") (pinfunction "PD3(TXD1/INT3)_21") (pintype "unspecified"))
    )
    (net (code "4") (name "Col2") (class "Default")
      (node (ref "SW11") (pin "1") (pinfunction "Col_1") (pintype "unspecified"))
      (node (ref "SW12") (pin "1") (pinfunction "Col_1") (pintype "unspecified"))
      (node (ref "SW13") (pin "1") (pinfunction "Col_1") (pintype "unspecified"))
      (node (ref "SW14") (pin "1") (pinfunction "Col_1") (pintype "unspecified"))
      (node (ref "SW15") (pin "1") (pinfunction "Col_1") (pintype "unspecified"))
      (node (ref "U1") (pin "20") (pinfunction "PD2(RXD1/INT2)_20") (pintype "unspecified"))
    )
    (net (code "5") (name "Col3") (class "Default")
      (node (ref "SW16") (pin "1") (pinfunction "Col_1") (pintype "unspecified"))
      (node (ref "SW17") (pin "1") (pinfunction "Col_1") (pintype "unspecified"))
      (node (ref "SW18") (pin "1") (pinfunction "Col_1") (pintype "unspecified"))
      (node (ref "SW19") (pin "1") (pinfunction "Col_1") (pintype "unspecified"))
      (node (ref "SW20") (pin "1") (pinfunction "Col_1") (pintype "unspecified"))
      (node (ref "U1") (pin "40") (pinfunction "PF1(ADC1)_40") (pintype "unspecified"))
    )
    (net (code "6") (name "Col4") (class "Default")
      (node (ref "SW21") (pin "1") (pinfunction "Col_1") (pintype "unspecified"))
      (node (ref "SW22") (pin "1") (pinfunction "Col_1") (pintype "unspecified"))
      (node (ref "SW23") (pin "1") (pinfunction "Col_1") (pintype "unspecified"))
      (node (ref "SW24") (pin "1") (pinfunction "Col_1") (pintype "unspecified"))
      (node (ref "SW25") (pin "1") (pinfunction "Col_1") (pintype "unspecified"))
      (node (ref "U1") (pin "39") (pinfunction "PF4(ADC4/TCK)_39") (pintype "unspecified"))
    )
    (net (code "7") (name "Col5") (class "Default")
      (node (ref "SW26") (pin "1") (pinfunction "Col_1") (pintype "unspecified"))
      (node (ref "SW27") (pin "1") (pinfunction "Col_1") (pintype "unspecified"))
      (node (ref "SW28") (pin "1") (pinfunction "Col_1") (pintype "unspecified"))
      (node (ref "SW29") (pin "1") (pinfunction "Col_1") (pintype "unspecified"))
      (node (ref "SW30") (pin "1") (pinfunction "Col_1") (pintype "unspecified"))
      (node (ref "U1") (pin "38") (pinfunction "PF5(ADC5/TMS)_38") (pintype "unspecified"))
    )
    (net (code "8") (name "Col6") (class "Default")
      (node (ref "SW31") (pin "1") (pinfunction "Col_1") (pintype "unspecified"))
      (node (ref "SW32") (pin "1") (pinfunction "Col_1") (pintype "unspecified"))
      (node (ref "SW33") (pin "1") (pinfunction "Col_1") (pintype "unspecified"))
      (node (ref "SW34") (pin "1") (pinfunction "Col_1") (pintype "unspecified"))
      (node (ref "SW35") (pin "1") (pinfunction "Col_1") (pintype "unspecified"))
      (node (ref "SW36") (pin "1") (pinfunction "Col_1") (pintype "unspecified"))
      (node (ref "SW37") (pin "1") (pinfunction "Col_1") (pintype "unspecified"))
      (node (ref "U1") (pin "37") (pinfunction "PF6(ADC6/TDO)_37") (pintype "unspecified"))
    )
    (net (code "9") (name "Col7") (class "Default")
      (node (ref "SW38") (pin "1") (pinfunction "Col_1") (pintype "unspecified"))
      (node (ref "SW39") (pin "1") (pinfunction "Col_1") (pintype "unspecified"))
      (node (ref "SW40") (pin "1") (pinfunction "Col_1") (pintype "unspecified"))
      (node (ref "SW41") (pin "1") (pinfunction "Col_1") (pintype "unspecified"))
      (node (ref "SW42") (pin "1") (pinfunction "Col_1") (pintype "unspecified"))
      (node (ref "U1") (pin "36") (pinfunction "PF7(ADC7/TDI)_36") (pintype "unspecified"))
    )
    (net (code "10") (name "Col8") (class "Default")
      (node (ref "SW43") (pin "1") (pinfunction "Col_1") (pintype "unspecified"))
      (node (ref "SW44") (pin "1") (pinfunction "Col_1") (pintype "unspecified"))
      (node (ref "SW45") (pin "1") (pinfunction "Col_1") (pintype "unspecified"))
      (node (ref "SW46") (pin "1") (pinfunction "Col_1") (pintype "unspecified"))
      (node (ref "SW47") (pin "1") (pinfunction "Col_1") (pintype "unspecified"))
      (node (ref "U1") (pin "32") (pinfunction "PC7(ICP3/CLK0/OC4A)_32") (pintype "unspecified"))
    )
    (net (code "11") (name "Col9") (class "Default")
      (node (ref "SW48") (pin "1") (pinfunction "Col_1") (pintype "unspecified"))
      (node (ref "SW49") (pin "1") (pinfunction "Col_1") (pintype "unspecified"))
      (node (ref "SW50") (pin "1") (pinfunction "Col_1") (pintype "unspecified"))
      (node (ref "SW51") (pin "1") (pinfunction "Col_1") (pintype "unspecified"))
      (node (ref "SW52") (pin "1") (pinfunction "Col_1") (pintype "unspecified"))
      (node (ref "U1") (pin "31") (pinfunction "PC6(OC3A/OC4A#)_31") (pintype "unspecified"))
    )
    (net (code "12") (name "Col10") (class "Default")
      (node (ref "SW53") (pin "1") (pinfunction "Col_1") (pintype "unspecified"))
      (node (ref "SW54") (pin "1") (pinfunction "Col_1") (pintype "unspecified"))
      (node (ref "SW55") (pin "1") (pinfunction "Col_1") (pintype "unspecified"))
      (node (ref "SW56") (pin "1") (pinfunction "Col_1") (pintype "unspecified"))
      (node (ref "SW57") (pin "1") (pinfunction "Col_1") (pintype "unspecified"))
      (node (ref "U1") (pin "30") (pinfunction "PB6(PCINT6/OC1B/OC4B/ADC13)_30") (pintype "unspecified"))
    )
    (net (code "13") (name "Col11") (class "Default")
      (node (ref "SW58") (pin "1") (pinfunction "Col_1") (pintype "unspecified"))
      (node (ref "SW59") (pin "1") (pinfunction "Col_1") (pintype "unspecified"))
      (node (ref "SW60") (pin "1") (pinfunction "Col_1") (pintype "unspecified"))
      (node (ref "SW61") (pin "1") (pinfunction "Col_1") (pintype "unspecified"))
      (node (ref "SW62") (pin "1") (pinfunction "Col_1") (pintype "unspecified"))
      (node (ref "U1") (pin "29") (pinfunction "PB5(PCINT5/OC1A/OC4B#/ADC12)_29") (pintype "unspecified"))
    )
    (net (code "14") (name "Col12") (class "Default")
      (node (ref "SW63") (pin "1") (pinfunction "Col_1") (pintype "unspecified"))
      (node (ref "SW64") (pin "1") (pinfunction "Col_1") (pintype "unspecified"))
      (node (ref "SW65") (pin "1") (pinfunction "Col_1") (pintype "unspecified"))
      (node (ref "SW66") (pin "1") (pinfunction "Col_1") (pintype "unspecified"))
      (node (ref "SW67") (pin "1") (pinfunction "Col_1") (pintype "unspecified"))
      (node (ref "U1") (pin "28") (pinfunction "PB4(PCINT4/ADC11)_28") (pintype "unspecified"))
    )
    (net (code "15") (name "Col13") (class "Default")
      (node (ref "ENC1") (pin "E") (pinfunction "E_E") (pintype "unspecified"))
      (node (ref "SW68") (pin "1") (pinfunction "Col_1") (pintype "unspecified"))
      (node (ref "SW69") (pin "1") (pinfunction "Col_1") (pintype "unspecified"))
      (node (ref "SW70") (pin "1") (pinfunction "Col_1") (pintype "unspecified"))
      (node (ref "SW71") (pin "1") (pinfunction "Col_1") (pintype "unspecified"))
      (node (ref "U1") (pin "27") (pinfunction "PD7(T0/OC4D/ADC10)_27") (pintype "unspecified"))
    )
    (net (code "16") (name "Din_N") (class "Default")
      (node (ref "ESD1") (pin "3") (pinfunction "I/O2_3") (pintype "unspecified"))
      (node (ref "USBC1") (pin "A7") (pinfunction "DN1_A7") (pintype "unspecified"))
      (node (ref "USBC1") (pin "B7") (pinfunction "DN2_B7") (pintype "unspecified"))
    )
    (net (code "17") (name "Din_P") (class "Default")
      (node (ref "ESD1") (pin "1") (pinfunction "I/O1_1") (pintype "unspecified"))
      (node (ref "USBC1") (pin "A6") (pinfunction "DP1_A6") (pintype "unspecified"))
      (node (ref "USBC1") (pin "B6") (pinfunction "DP2_B6") (pintype "unspecified"))
    )
    (net (code "18") (name "Dout_N") (class "Default")
      (node (ref "ESD1") (pin "4") (pinfunction "I/O2_4") (pintype "unspecified"))
      (node (ref "R70") (pin "2") (pinfunction "2_2") (pintype "input"))
    )
    (net (code "19") (name "Dout_P") (class "Default")
      (node (ref "ESD1") (pin "6") (pinfunction "I/O1_6") (pintype "unspecified"))
      (node (ref "R71") (pin "2") (pinfunction "2_2") (pintype "input"))
    )
    (net (code "20") (name "GND") (class "Default")
      (node (ref "BUTTON") (pin "3") (pinfunction "C_3") (pintype "unspecified"))
      (node (ref "BUTTON") (pin "4") (pinfunction "D_4") (pintype "unspecified"))
      (node (ref "C1") (pin "2") (pinfunction "2_2") (pintype "unspecified"))
      (node (ref "C10") (pin "1") (pinfunction "1_1") (pintype "input"))
      (node (ref "C11") (pin "1") (pinfunction "1_1") (pintype "input"))
      (node (ref "C12") (pin "1") (pinfunction "1_1") (pintype "input"))
      (node (ref "C2") (pin "1") (pinfunction "1_1") (pintype "unspecified"))
      (node (ref "C3") (pin "1") (pinfunction "1_1") (pintype "unspecified"))
      (node (ref "C4") (pin "1") (pinfunction "1_1") (pintype "unspecified"))
      (node (ref "C5") (pin "1") (pinfunction "1_1") (pintype "unspecified"))
      (node (ref "C6") (pin "1") (pinfunction "1_1") (pintype "unspecified"))
      (node (ref "C7") (pin "1") (pinfunction "1_1") (pintype "input"))
      (node (ref "C8") (pin "1") (pinfunction "1_1") (pintype "unspecified"))
      (node (ref "C9") (pin "2") (pinfunction "2_2") (pintype "unspecified"))
      (node (ref "DIP") (pin "2") (pinfunction "A2_2") (pintype "input"))
      (node (ref "ENC1") (pin "C") (pinfunction "C_C") (pintype "unspecified"))
      (node (ref "ESD1") (pin "2") (pinfunction "GND_2") (pintype "unspecified"))
      (node (ref "OLED1") (pin "4") (pinfunction "GND_4") (pintype "unspecified"))
      (node (ref "R1") (pin "1") (pinfunction "1_1") (pintype "unspecified"))
      (node (ref "R10") (pin "1") (pinfunction "1_1") (pintype "unspecified"))
      (node (ref "R11") (pin "1") (pinfunction "1_1") (pintype "unspecified"))
      (node (ref "R12") (pin "1") (pinfunction "1_1") (pintype "unspecified"))
      (node (ref "R13") (pin "1") (pinfunction "1_1") (pintype "unspecified"))
      (node (ref "R14") (pin "1") (pinfunction "1_1") (pintype "unspecified"))
      (node (ref "R15") (pin "1") (pinfunction "1_1") (pintype "unspecified"))
      (node (ref "R16") (pin "1") (pinfunction "1_1") (pintype "unspecified"))
      (node (ref "R17") (pin "1") (pinfunction "1_1") (pintype "unspecified"))
      (node (ref "R18") (pin "1") (pinfunction "1_1") (pintype "unspecified"))
      (node (ref "R19") (pin "1") (pinfunction "1_1") (pintype "unspecified"))
      (node (ref "R2") (pin "1") (pinfunction "1_1") (pintype "unspecified"))
      (node (ref "R20") (pin "1") (pinfunction "1_1") (pintype "unspecified"))
      (node (ref "R21") (pin "1") (pinfunction "1_1") (pintype "unspecified"))
      (node (ref "R22") (pin "1") (pinfunction "1_1") (pintype "unspecified"))
      (node (ref "R23") (pin "1") (pinfunction "1_1") (pintype "unspecified"))
      (node (ref "R24") (pin "1") (pinfunction "1_1") (pintype "unspecified"))
      (node (ref "R25") (pin "1") (pinfunction "1_1") (pintype "unspecified"))
      (node (ref "R26") (pin "1") (pinfunction "1_1") (pintype "unspecified"))
      (node (ref "R27") (pin "1") (pinfunction "1_1") (pintype "unspecified"))
      (node (ref "R28") (pin "1") (pinfunction "1_1") (pintype "unspecified"))
      (node (ref "R29") (pin "1") (pinfunction "1_1") (pintype "unspecified"))
      (node (ref "R3") (pin "1") (pinfunction "1_1") (pintype "unspecified"))
      (node (ref "R30") (pin "1") (pinfunction "1_1") (pintype "unspecified"))
      (node (ref "R31") (pin "1") (pinfunction "1_1") (pintype "unspecified"))
      (node (ref "R32") (pin "1") (pinfunction "1_1") (pintype "unspecified"))
      (node (ref "R33") (pin "1") (pinfunction "1_1") (pintype "unspecified"))
      (node (ref "R34") (pin "1") (pinfunction "1_1") (pintype "unspecified"))
      (node (ref "R35") (pin "1") (pinfunction "1_1") (pintype "unspecified"))
      (node (ref "R36") (pin "1") (pinfunction "1_1") (pintype "unspecified"))
      (node (ref "R37") (pin "1") (pinfunction "1_1") (pintype "unspecified"))
      (node (ref "R38") (pin "1") (pinfunction "1_1") (pintype "unspecified"))
      (node (ref "R39") (pin "1") (pinfunction "1_1") (pintype "unspecified"))
      (node (ref "R4") (pin "1") (pinfunction "1_1") (pintype "unspecified"))
      (node (ref "R40") (pin "1") (pinfunction "1_1") (pintype "unspecified"))
      (node (ref "R41") (pin "1") (pinfunction "1_1") (pintype "unspecified"))
      (node (ref "R42") (pin "1") (pinfunction "1_1") (pintype "unspecified"))
      (node (ref "R43") (pin "1") (pinfunction "1_1") (pintype "unspecified"))
      (node (ref "R44") (pin "1") (pinfunction "1_1") (pintype "unspecified"))
      (node (ref "R45") (pin "1") (pinfunction "1_1") (pintype "unspecified"))
      (node (ref "R46") (pin "1") (pinfunction "1_1") (pintype "unspecified"))
      (node (ref "R47") (pin "1") (pinfunction "1_1") (pintype "unspecified"))
      (node (ref "R48") (pin "1") (pinfunction "1_1") (pintype "unspecified"))
      (node (ref "R49") (pin "1") (pinfunction "1_1") (pintype "unspecified"))
      (node (ref "R5") (pin "1") (pinfunction "1_1") (pintype "unspecified"))
      (node (ref "R50") (pin "1") (pinfunction "1_1") (pintype "unspecified"))
      (node (ref "R51") (pin "1") (pinfunction "1_1") (pintype "unspecified"))
      (node (ref "R52") (pin "1") (pinfunction "1_1") (pintype "unspecified"))
      (node (ref "R53") (pin "1") (pinfunction "1_1") (pintype "unspecified"))
      (node (ref "R54") (pin "1") (pinfunction "1_1") (pintype "unspecified"))
      (node (ref "R55") (pin "1") (pinfunction "1_1") (pintype "unspecified"))
      (node (ref "R56") (pin "1") (pinfunction "1_1") (pintype "unspecified"))
      (node (ref "R57") (pin "1") (pinfunction "1_1") (pintype "unspecified"))
      (node (ref "R58") (pin "1") (pinfunction "1_1") (pintype "unspecified"))
      (node (ref "R59") (pin "1") (pinfunction "1_1") (pintype "unspecified"))
      (node (ref "R6") (pin "1") (pinfunction "1_1") (pintype "unspecified"))
      (node (ref "R60") (pin "1") (pinfunction "1_1") (pintype "unspecified"))
      (node (ref "R61") (pin "1") (pinfunction "1_1") (pintype "unspecified"))
      (node (ref "R62") (pin "1") (pinfunction "1_1") (pintype "unspecified"))
      (node (ref "R63") (pin "1") (pinfunction "1_1") (pintype "unspecified"))
      (node (ref "R64") (pin "1") (pinfunction "1_1") (pintype "unspecified"))
      (node (ref "R65") (pin "1") (pinfunction "1_1") (pintype "unspecified"))
      (node (ref "R66") (pin "1") (pinfunction "1_1") (pintype "unspecified"))
      (node (ref "R67") (pin "1") (pinfunction "1_1") (pintype "unspecified"))
      (node (ref "R68") (pin "1") (pinfunction "1_1") (pintype "unspecified"))
      (node (ref "R69") (pin "1") (pinfunction "1_1") (pintype "unspecified"))
      (node (ref "R7") (pin "1") (pinfunction "1_1") (pintype "unspecified"))
      (node (ref "R72") (pin "1") (pinfunction "1_1") (pintype "input"))
      (node (ref "R73") (pin "1") (pinfunction "1_1") (pintype "unspecified"))
      (node (ref "R74") (pin "2") (pinfunction "2_2") (pintype "unspecified"))
      (node (ref "R75") (pin "1") (pinfunction "1_1") (pintype "unspecified"))
      (node (ref "R8") (pin "1") (pinfunction "1_1") (pintype "unspecified"))
      (node (ref "R9") (pin "1") (pinfunction "1_1") (pintype "unspecified"))
      (node (ref "STO1") (pin "1") (pinfunction "Standoff_1") (pintype "unspecified"))
      (node (ref "STO2") (pin "1") (pinfunction "Standoff_1") (pintype "unspecified"))
      (node (ref "STO3") (pin "1") (pinfunction "Standoff_1") (pintype "unspecified"))
      (node (ref "STO4") (pin "1") (pinfunction "Standoff_1") (pintype "unspecified"))
      (node (ref "STO5") (pin "1") (pinfunction "Standoff_1") (pintype "unspecified"))
      (node (ref "STO6") (pin "1") (pinfunction "Standoff_1") (pintype "unspecified"))
      (node (ref "STO7") (pin "1") (pinfunction "Standoff_1") (pintype "unspecified"))
      (node (ref "U1") (pin "15") (pinfunction "GND_15") (pintype "unspecified"))
      (node (ref "U1") (pin "23") (pinfunction "GND_23") (pintype "unspecified"))
      (node (ref "U1") (pin "35") (pinfunction "GND_35") (pintype "unspecified"))
      (node (ref "U1") (pin "43") (pinfunction "GND_43") (pintype "unspecified"))
      (node (ref "U1") (pin "45") (pinfunction "EP_45") (pintype "unspecified"))
      (node (ref "U1") (pin "5") (pinfunction "UGnd_5") (pintype "unspecified"))
      (node (ref "U2") (pin "4") (pinfunction "._4") (pintype "unspecified"))
      (node (ref "USBC1") (pin "A1") (pinfunction "GND_A1") (pintype "unspecified"))
      (node (ref "USBC1") (pin "A12") (pinfunction "GND_A12") (pintype "unspecified"))
      (node (ref "X1") (pin "2") (pinfunction "GND_2") (pintype "unspecified"))
      (node (ref "X1") (pin "4") (pinfunction "GND_4") (pintype "unspecified"))
    )
    (net (code "21") (name "Net-(D1-A)") (class "Default")
      (node (ref "D1") (pin "2") (pinfunction "A_2") (pintype "unspecified"))
      (node (ref "SW1") (pin "2") (pinfunction "Row_2") (pintype "unspecified"))
    )
    (net (code "22") (name "Net-(D2-A)") (class "Default")
      (node (ref "D2") (pin "2") (pinfunction "A_2") (pintype "unspecified"))
      (node (ref "SW2") (pin "2") (pinfunction "Row_2") (pintype "unspecified"))
    )
    (net (code "23") (name "Net-(D3-A)") (class "Default")
      (node (ref "D3") (pin "2") (pinfunction "A_2") (pintype "unspecified"))
      (node (ref "SW3") (pin "2") (pinfunction "Row_2") (pintype "unspecified"))
    )
    (net (code "24") (name "Net-(D4-A)") (class "Default")
      (node (ref "D4") (pin "2") (pinfunction "A_2") (pintype "unspecified"))
      (node (ref "SW4") (pin "2") (pinfunction "Row_2") (pintype "unspecified"))
    )
    (net (code "25") (name "Net-(D5-A)") (class "Default")
      (node (ref "D5") (pin "2") (pinfunction "A_2") (pintype "unspecified"))
      (node (ref "SW5") (pin "2") (pinfunction "Row_2") (pintype "unspecified"))
    )
    (net (code "26") (name "Net-(D6-A)") (class "Default")
      (node (ref "D6") (pin "2") (pinfunction "A_2") (pintype "unspecified"))
      (node (ref "SW6") (pin "2") (pinfunction "Row_2") (pintype "unspecified"))
    )
    (net (code "27") (name "Net-(D7-A)") (class "Default")
      (node (ref "D7") (pin "2") (pinfunction "A_2") (pintype "unspecified"))
      (node (ref "SW7") (pin "2") (pinfunction "Row_2") (pintype "unspecified"))
    )
    (net (code "28") (name "Net-(D8-A)") (class "Default")
      (node (ref "D8") (pin "2") (pinfunction "A_2") (pintype "unspecified"))
      (node (ref "SW8") (pin "2") (pinfunction "Row_2") (pintype "unspecified"))
    )
    (net (code "29") (name "Net-(D9-A)") (class "Default")
      (node (ref "D9") (pin "2") (pinfunction "A_2") (pintype "unspecified"))
      (node (ref "SW9") (pin "2") (pinfunction "Row_2") (pintype "unspecified"))
    )
    (net (code "30") (name "Net-(D10-A)") (class "Default")
      (node (ref "D10") (pin "2") (pinfunction "A_2") (pintype "unspecified"))
      (node (ref "SW10") (pin "2") (pinfunction "Row_2") (pintype "unspecified"))
    )
    (net (code "31") (name "Net-(D11-A)") (class "Default")
      (node (ref "D11") (pin "2") (pinfunction "A_2") (pintype "unspecified"))
      (node (ref "SW11") (pin "2") (pinfunction "Row_2") (pintype "unspecified"))
    )
    (net (code "32") (name "Net-(D12-A)") (class "Default")
      (node (ref "D12") (pin "2") (pinfunction "A_2") (pintype "unspecified"))
      (node (ref "SW12") (pin "2") (pinfunction "Row_2") (pintype "unspecified"))
    )
    (net (code "33") (name "Net-(D13-A)") (class "Default")
      (node (ref "D13") (pin "2") (pinfunction "A_2") (pintype "unspecified"))
      (node (ref "SW13") (pin "2") (pinfunction "Row_2") (pintype "unspecified"))
    )
    (net (code "34") (name "Net-(D14-A)") (class "Default")
      (node (ref "D14") (pin "2") (pinfunction "A_2") (pintype "unspecified"))
      (node (ref "SW14") (pin "2") (pinfunction "Row_2") (pintype "unspecified"))
    )
    (net (code "35") (name "Net-(D15-A)") (class "Default")
      (node (ref "D15") (pin "2") (pinfunction "A_2") (pintype "unspecified"))
      (node (ref "SW15") (pin "2") (pinfunction "Row_2") (pintype "unspecified"))
    )
    (net (code "36") (name "Net-(D16-A)") (class "Default")
      (node (ref "D16") (pin "2") (pinfunction "A_2") (pintype "unspecified"))
      (node (ref "SW16") (pin "2") (pinfunction "Row_2") (pintype "unspecified"))
    )
    (net (code "37") (name "Net-(D17-A)") (class "Default")
      (node (ref "D17") (pin "2") (pinfunction "A_2") (pintype "unspecified"))
      (node (ref "SW17") (pin "2") (pinfunction "Row_2") (pintype "unspecified"))
    )
    (net (code "38") (name "Net-(D18-A)") (class "Default")
      (node (ref "D18") (pin "2") (pinfunction "A_2") (pintype "unspecified"))
      (node (ref "SW18") (pin "2") (pinfunction "Row_2") (pintype "unspecified"))
    )
    (net (code "39") (name "Net-(D19-A)") (class "Default")
      (node (ref "D19") (pin "2") (pinfunction "A_2") (pintype "unspecified"))
      (node (ref "SW19") (pin "2") (pinfunction "Row_2") (pintype "unspecified"))
    )
    (net (code "40") (name "Net-(D20-A)") (class "Default")
      (node (ref "D20") (pin "2") (pinfunction "A_2") (pintype "unspecified"))
      (node (ref "SW20") (pin "2") (pinfunction "Row_2") (pintype "unspecified"))
    )
    (net (code "41") (name "Net-(D21-A)") (class "Default")
      (node (ref "D21") (pin "2") (pinfunction "A_2") (pintype "unspecified"))
      (node (ref "SW21") (pin "2") (pinfunction "Row_2") (pintype "unspecified"))
    )
    (net (code "42") (name "Net-(D22-A)") (class "Default")
      (node (ref "D22") (pin "2") (pinfunction "A_2") (pintype "unspecified"))
      (node (ref "SW22") (pin "2") (pinfunction "Row_2") (pintype "unspecified"))
    )
    (net (code "43") (name "Net-(D23-A)") (class "Default")
      (node (ref "D23") (pin "2") (pinfunction "A_2") (pintype "unspecified"))
      (node (ref "SW23") (pin "2") (pinfunction "Row_2") (pintype "unspecified"))
    )
    (net (code "44") (name "Net-(D24-A)") (class "Default")
      (node (ref "D24") (pin "2") (pinfunction "A_2") (pintype "unspecified"))
      (node (ref "SW24") (pin "2") (pinfunction "Row_2") (pintype "unspecified"))
    )
    (net (code "45") (name "Net-(D25-A)") (class "Default")
      (node (ref "D25") (pin "2") (pinfunction "A_2") (pintype "unspecified"))
      (node (ref "SW25") (pin "2") (pinfunction "Row_2") (pintype "unspecified"))
    )
    (net (code "46") (name "Net-(D26-A)") (class "Default")
      (node (ref "D26") (pin "2") (pinfunction "A_2") (pintype "unspecified"))
      (node (ref "SW26") (pin "2") (pinfunction "Row_2") (pintype "unspecified"))
    )
    (net (code "47") (name "Net-(D27-A)") (class "Default")
      (node (ref "D27") (pin "2") (pinfunction "A_2") (pintype "unspecified"))
      (node (ref "SW27") (pin "2") (pinfunction "Row_2") (pintype "unspecified"))
    )
    (net (code "48") (name "Net-(D28-A)") (class "Default")
      (node (ref "D28") (pin "2") (pinfunction "A_2") (pintype "unspecified"))
      (node (ref "SW28") (pin "2") (pinfunction "Row_2") (pintype "unspecified"))
    )
    (net (code "49") (name "Net-(D29-A)") (class "Default")
      (node (ref "D29") (pin "2") (pinfunction "A_2") (pintype "unspecified"))
      (node (ref "SW29") (pin "2") (pinfunction "Row_2") (pintype "unspecified"))
    )
    (net (code "50") (name "Net-(D30-A)") (class "Default")
      (node (ref "D30") (pin "2") (pinfunction "A_2") (pintype "unspecified"))
      (node (ref "SW30") (pin "2") (pinfunction "Row_2") (pintype "unspecified"))
    )
    (net (code "51") (name "Net-(D31-A)") (class "Default")
      (node (ref "D31") (pin "2") (pinfunction "A_2") (pintype "unspecified"))
      (node (ref "SW31") (pin "2") (pinfunction "Row_2") (pintype "unspecified"))
      (node (ref "SW32") (pin "2") (pinfunction "Row_2") (pintype "unspecified"))
    )
    (net (code "52") (name "Net-(D32-A)") (class "Default")
      (node (ref "D32") (pin "2") (pinfunction "A_2") (pintype "unspecified"))
      (node (ref "SW33") (pin "2") (pinfunction "Row_2") (pintype "unspecified"))
    )
    (net (code "53") (name "Net-(D33-A)") (class "Default")
      (node (ref "D33") (pin "2") (pinfunction "A_2") (pintype "unspecified"))
      (node (ref "SW34") (pin "2") (pinfunction "Row_2") (pintype "unspecified"))
    )
    (net (code "54") (name "Net-(D34-A)") (class "Default")
      (node (ref "D34") (pin "2") (pinfunction "A_2") (pintype "unspecified"))
      (node (ref "SW35") (pin "2") (pinfunction "Row_2") (pintype "unspecified"))
    )
    (net (code "55") (name "Net-(D35-A)") (class "Default")
      (node (ref "D35") (pin "2") (pinfunction "A_2") (pintype "unspecified"))
      (node (ref "SW36") (pin "2") (pinfunction "Row_2") (pintype "unspecified"))
      (node (ref "SW37") (pin "2") (pinfunction "Row_2") (pintype "unspecified"))
    )
    (net (code "56") (name "Net-(D36-A)") (class "Default")
      (node (ref "D36") (pin "2") (pinfunction "A_2") (pintype "unspecified"))
      (node (ref "SW38") (pin "2") (pinfunction "Row_2") (pintype "unspecified"))
    )
    (net (code "57") (name "Net-(D37-A)") (class "Default")
      (node (ref "D37") (pin "2") (pinfunction "A_2") (pintype "unspecified"))
      (node (ref "SW39") (pin "2") (pinfunction "Row_2") (pintype "unspecified"))
    )
    (net (code "58") (name "Net-(D38-A)") (class "Default")
      (node (ref "D38") (pin "2") (pinfunction "A_2") (pintype "unspecified"))
      (node (ref "SW40") (pin "2") (pinfunction "Row_2") (pintype "unspecified"))
    )
    (net (code "59") (name "Net-(D39-A)") (class "Default")
      (node (ref "D39") (pin "2") (pinfunction "A_2") (pintype "unspecified"))
      (node (ref "SW41") (pin "2") (pinfunction "Row_2") (pintype "unspecified"))
    )
    (net (code "60") (name "Net-(D40-A)") (class "Default")
      (node (ref "D40") (pin "2") (pinfunction "A_2") (pintype "unspecified"))
      (node (ref "SW42") (pin "2") (pinfunction "Row_2") (pintype "unspecified"))
    )
    (net (code "61") (name "Net-(D41-A)") (class "Default")
      (node (ref "D41") (pin "2") (pinfunction "A_2") (pintype "unspecified"))
      (node (ref "SW43") (pin "2") (pinfunction "Row_2") (pintype "unspecified"))
    )
    (net (code "62") (name "Net-(D42-A)") (class "Default")
      (node (ref "D42") (pin "2") (pinfunction "A_2") (pintype "unspecified"))
      (node (ref "SW44") (pin "2") (pinfunction "Row_2") (pintype "unspecified"))
    )
    (net (code "63") (name "Net-(D43-A)") (class "Default")
      (node (ref "D43") (pin "2") (pinfunction "A_2") (pintype "unspecified"))
      (node (ref "SW45") (pin "2") (pinfunction "Row_2") (pintype "unspecified"))
    )
    (net (code "64") (name "Net-(D44-A)") (class "Default")
      (node (ref "D44") (pin "2") (pinfunction "A_2") (pintype "unspecified"))
      (node (ref "SW46") (pin "2") (pinfunction "Row_2") (pintype "unspecified"))
    )
    (net (code "65") (name "Net-(D45-A)") (class "Default")
      (node (ref "D45") (pin "2") (pinfunction "A_2") (pintype "unspecified"))
      (node (ref "SW47") (pin "2") (pinfunction "Row_2") (pintype "unspecified"))
    )
    (net (code "66") (name "Net-(D46-A)") (class "Default")
      (node (ref "D46") (pin "2") (pinfunction "A_2") (pintype "unspecified"))
      (node (ref "SW48") (pin "2") (pinfunction "Row_2") (pintype "unspecified"))
    )
    (net (code "67") (name "Net-(D47-A)") (class "Default")
      (node (ref "D47") (pin "2") (pinfunction "A_2") (pintype "unspecified"))
      (node (ref "SW49") (pin "2") (pinfunction "Row_2") (pintype "unspecified"))
    )
    (net (code "68") (name "Net-(D48-A)") (class "Default")
      (node (ref "D48") (pin "2") (pinfunction "A_2") (pintype "unspecified"))
      (node (ref "SW50") (pin "2") (pinfunction "Row_2") (pintype "unspecified"))
    )
    (net (code "69") (name "Net-(D49-A)") (class "Default")
      (node (ref "D49") (pin "2") (pinfunction "A_2") (pintype "unspecified"))
      (node (ref "SW51") (pin "2") (pinfunction "Row_2") (pintype "unspecified"))
    )
    (net (code "70") (name "Net-(D50-A)") (class "Default")
      (node (ref "D50") (pin "2") (pinfunction "A_2") (pintype "unspecified"))
      (node (ref "SW52") (pin "2") (pinfunction "Row_2") (pintype "unspecified"))
    )
    (net (code "71") (name "Net-(D51-A)") (class "Default")
      (node (ref "D51") (pin "2") (pinfunction "A_2") (pintype "unspecified"))
      (node (ref "SW53") (pin "2") (pinfunction "Row_2") (pintype "unspecified"))
    )
    (net (code "72") (name "Net-(D52-A)") (class "Default")
      (node (ref "D52") (pin "2") (pinfunction "A_2") (pintype "unspecified"))
      (node (ref "SW54") (pin "2") (pinfunction "Row_2") (pintype "unspecified"))
    )
    (net (code "73") (name "Net-(D53-A)") (class "Default")
      (node (ref "D53") (pin "2") (pinfunction "A_2") (pintype "unspecified"))
      (node (ref "SW55") (pin "2") (pinfunction "Row_2") (pintype "unspecified"))
    )
    (net (code "74") (name "Net-(D54-A)") (class "Default")
      (node (ref "D54") (pin "2") (pinfunction "A_2") (pintype "unspecified"))
      (node (ref "SW56") (pin "2") (pinfunction "Row_2") (pintype "unspecified"))
    )
    (net (code "75") (name "Net-(D55-A)") (class "Default")
      (node (ref "D55") (pin "2") (pinfunction "A_2") (pintype "unspecified"))
      (node (ref "SW57") (pin "2") (pinfunction "Row_2") (pintype "unspecified"))
    )
    (net (code "76") (name "Net-(D56-A)") (class "Default")
      (node (ref "D56") (pin "2") (pinfunction "A_2") (pintype "unspecified"))
      (node (ref "SW58") (pin "2") (pinfunction "Row_2") (pintype "unspecified"))
    )
    (net (code "77") (name "Net-(D57-A)") (class "Default")
      (node (ref "D57") (pin "2") (pinfunction "A_2") (pintype "unspecified"))
      (node (ref "SW59") (pin "2") (pinfunction "Row_2") (pintype "unspecified"))
    )
    (net (code "78") (name "Net-(D58-A)") (class "Default")
      (node (ref "D58") (pin "2") (pinfunction "A_2") (pintype "unspecified"))
      (node (ref "SW60") (pin "2") (pinfunction "Row_2") (pintype "unspecified"))
    )
    (net (code "79") (name "Net-(D59-A)") (class "Default")
      (node (ref "D59") (pin "2") (pinfunction "A_2") (pintype "unspecified"))
      (node (ref "SW61") (pin "2") (pinfunction "Row_2") (pintype "unspecified"))
    )
    (net (code "80") (name "Net-(D60-A)") (class "Default")
      (node (ref "D60") (pin "2") (pinfunction "A_2") (pintype "unspecified"))
      (node (ref "SW62") (pin "2") (pinfunction "Row_2") (pintype "unspecified"))
    )
    (net (code "81") (name "Net-(D61-A)") (class "Default")
      (node (ref "D61") (pin "2") (pinfunction "A_2") (pintype "unspecified"))
      (node (ref "SW63") (pin "2") (pinfunction "Row_2") (pintype "unspecified"))
    )
    (net (code "82") (name "Net-(D62-A)") (class "Default")
      (node (ref "D62") (pin "2") (pinfunction "A_2") (pintype "unspecified"))
      (node (ref "SW64") (pin "2") (pinfunction "Row_2") (pintype "unspecified"))
    )
    (net (code "83") (name "Net-(D63-A)") (class "Default")
      (node (ref "D63") (pin "2") (pinfunction "A_2") (pintype "unspecified"))
      (node (ref "SW65") (pin "2") (pinfunction "Row_2") (pintype "unspecified"))
    )
    (net (code "84") (name "Net-(D64-A)") (class "Default")
      (node (ref "D64") (pin "2") (pinfunction "A_2") (pintype "unspecified"))
      (node (ref "SW66") (pin "2") (pinfunction "Row_2") (pintype "unspecified"))
    )
    (net (code "85") (name "Net-(D65-A)") (class "Default")
      (node (ref "D65") (pin "2") (pinfunction "A_2") (pintype "unspecified"))
      (node (ref "SW67") (pin "2") (pinfunction "Row_2") (pintype "unspecified"))
    )
    (net (code "86") (name "Net-(D66-A)") (class "Default")
      (node (ref "D66") (pin "2") (pinfunction "A_2") (pintype "unspecified"))
      (node (ref "ENC1") (pin "D") (pinfunction "D_D") (pintype "unspecified"))
    )
    (net (code "87") (name "Net-(D67-A)") (class "Default")
      (node (ref "D67") (pin "2") (pinfunction "A_2") (pintype "unspecified"))
      (node (ref "SW68") (pin "2") (pinfunction "Row_2") (pintype "unspecified"))
    )
    (net (code "88") (name "Net-(D68-A)") (class "Default")
      (node (ref "D68") (pin "2") (pinfunction "A_2") (pintype "unspecified"))
      (node (ref "SW69") (pin "2") (pinfunction "Row_2") (pintype "unspecified"))
    )
    (net (code "89") (name "Net-(D69-A)") (class "Default")
      (node (ref "D69") (pin "2") (pinfunction "A_2") (pintype "unspecified"))
      (node (ref "SW70") (pin "2") (pinfunction "Row_2") (pintype "unspecified"))
    )
    (net (code "90") (name "Net-(D70-A)") (class "Default")
      (node (ref "D70") (pin "2") (pinfunction "A_2") (pintype "unspecified"))
      (node (ref "SW71") (pin "2") (pinfunction "Row_2") (pintype "unspecified"))
    )
    (net (code "91") (name "Net-(PWR-K)") (class "Default")
      (node (ref "PWR") (pin "2") (pinfunction "K_2") (pintype "unspecified"))
      (node (ref "R73") (pin "2") (pinfunction "2_2") (pintype "unspecified"))
    )
    (net (code "92") (name "Net-(SW1-GND-LED)") (class "Default")
      (node (ref "R1") (pin "2") (pinfunction "2_2") (pintype "unspecified"))
      (node (ref "SW1") (pin "4") (pinfunction "GND-LED_4") (pintype "unspecified"))
    )
    (net (code "93") (name "Net-(SW2-GND-LED)") (class "Default")
      (node (ref "R2") (pin "2") (pinfunction "2_2") (pintype "unspecified"))
      (node (ref "SW2") (pin "4") (pinfunction "GND-LED_4") (pintype "unspecified"))
    )
    (net (code "94") (name "Net-(SW3-GND-LED)") (class "Default")
      (node (ref "R3") (pin "2") (pinfunction "2_2") (pintype "unspecified"))
      (node (ref "SW3") (pin "4") (pinfunction "GND-LED_4") (pintype "unspecified"))
    )
    (net (code "95") (name "Net-(SW4-GND-LED)") (class "Default")
      (node (ref "R4") (pin "2") (pinfunction "2_2") (pintype "unspecified"))
      (node (ref "SW4") (pin "4") (pinfunction "GND-LED_4") (pintype "unspecified"))
    )
    (net (code "96") (name "Net-(SW5-GND-LED)") (class "Default")
      (node (ref "R5") (pin "2") (pinfunction "2_2") (pintype "unspecified"))
      (node (ref "SW5") (pin "4") (pinfunction "GND-LED_4") (pintype "unspecified"))
    )
    (net (code "97") (name "Net-(SW6-GND-LED)") (class "Default")
      (node (ref "R6") (pin "2") (pinfunction "2_2") (pintype "unspecified"))
      (node (ref "SW6") (pin "4") (pinfunction "GND-LED_4") (pintype "unspecified"))
    )
    (net (code "98") (name "Net-(SW7-GND-LED)") (class "Default")
      (node (ref "R7") (pin "2") (pinfunction "2_2") (pintype "unspecified"))
      (node (ref "SW7") (pin "4") (pinfunction "GND-LED_4") (pintype "unspecified"))
    )
    (net (code "99") (name "Net-(SW8-GND-LED)") (class "Default")
      (node (ref "R8") (pin "2") (pinfunction "2_2") (pintype "unspecified"))
      (node (ref "SW8") (pin "4") (pinfunction "GND-LED_4") (pintype "unspecified"))
    )
    (net (code "100") (name "Net-(SW9-GND-LED)") (class "Default")
      (node (ref "R9") (pin "2") (pinfunction "2_2") (pintype "unspecified"))
      (node (ref "SW9") (pin "4") (pinfunction "GND-LED_4") (pintype "unspecified"))
    )
    (net (code "101") (name "Net-(SW10-GND-LED)") (class "Default")
      (node (ref "R10") (pin "2") (pinfunction "2_2") (pintype "unspecified"))
      (node (ref "SW10") (pin "4") (pinfunction "GND-LED_4") (pintype "unspecified"))
    )
    (net (code "102") (name "Net-(SW11-GND-LED)") (class "Default")
      (node (ref "R11") (pin "2") (pinfunction "2_2") (pintype "unspecified"))
      (node (ref "SW11") (pin "4") (pinfunction "GND-LED_4") (pintype "unspecified"))
    )
    (net (code "103") (name "Net-(SW12-GND-LED)") (class "Default")
      (node (ref "R12") (pin "2") (pinfunction "2_2") (pintype "unspecified"))
      (node (ref "SW12") (pin "4") (pinfunction "GND-LED_4") (pintype "unspecified"))
    )
    (net (code "104") (name "Net-(SW13-GND-LED)") (class "Default")
      (node (ref "R13") (pin "2") (pinfunction "2_2") (pintype "unspecified"))
      (node (ref "SW13") (pin "4") (pinfunction "GND-LED_4") (pintype "unspecified"))
    )
    (net (code "105") (name "Net-(SW14-GND-LED)") (class "Default")
      (node (ref "R14") (pin "2") (pinfunction "2_2") (pintype "unspecified"))
      (node (ref "SW14") (pin "4") (pinfunction "GND-LED_4") (pintype "unspecified"))
    )
    (net (code "106") (name "Net-(SW15-GND-LED)") (class "Default")
      (node (ref "R15") (pin "2") (pinfunction "2_2") (pintype "unspecified"))
      (node (ref "SW15") (pin "4") (pinfunction "GND-LED_4") (pintype "unspecified"))
    )
    (net (code "107") (name "Net-(SW16-GND-LED)") (class "Default")
      (node (ref "R16") (pin "2") (pinfunction "2_2") (pintype "unspecified"))
      (node (ref "SW16") (pin "4") (pinfunction "GND-LED_4") (pintype "unspecified"))
    )
    (net (code "108") (name "Net-(SW17-GND-LED)") (class "Default")
      (node (ref "R17") (pin "2") (pinfunction "2_2") (pintype "unspecified"))
      (node (ref "SW17") (pin "4") (pinfunction "GND-LED_4") (pintype "unspecified"))
    )
    (net (code "109") (name "Net-(SW18-GND-LED)") (class "Default")
      (node (ref "R18") (pin "2") (pinfunction "2_2") (pintype "unspecified"))
      (node (ref "SW18") (pin "4") (pinfunction "GND-LED_4") (pintype "unspecified"))
    )
    (net (code "110") (name "Net-(SW19-GND-LED)") (class "Default")
      (node (ref "R19") (pin "2") (pinfunction "2_2") (pintype "unspecified"))
      (node (ref "SW19") (pin "4") (pinfunction "GND-LED_4") (pintype "unspecified"))
    )
    (net (code "111") (name "Net-(SW20-GND-LED)") (class "Default")
      (node (ref "R20") (pin "2") (pinfunction "2_2") (pintype "unspecified"))
      (node (ref "SW20") (pin "4") (pinfunction "GND-LED_4") (pintype "unspecified"))
    )
    (net (code "112") (name "Net-(SW21-GND-LED)") (class "Default")
      (node (ref "R21") (pin "2") (pinfunction "2_2") (pintype "unspecified"))
      (node (ref "SW21") (pin "4") (pinfunction "GND-LED_4") (pintype "unspecified"))
    )
    (net (code "113") (name "Net-(SW22-GND-LED)") (class "Default")
      (node (ref "R22") (pin "2") (pinfunction "2_2") (pintype "unspecified"))
      (node (ref "SW22") (pin "4") (pinfunction "GND-LED_4") (pintype "unspecified"))
    )
    (net (code "114") (name "Net-(SW23-GND-LED)") (class "Default")
      (node (ref "R23") (pin "2") (pinfunction "2_2") (pintype "unspecified"))
      (node (ref "SW23") (pin "4") (pinfunction "GND-LED_4") (pintype "unspecified"))
    )
    (net (code "115") (name "Net-(SW24-GND-LED)") (class "Default")
      (node (ref "R24") (pin "2") (pinfunction "2_2") (pintype "unspecified"))
      (node (ref "SW24") (pin "4") (pinfunction "GND-LED_4") (pintype "unspecified"))
    )
    (net (code "116") (name "Net-(SW25-GND-LED)") (class "Default")
      (node (ref "R25") (pin "2") (pinfunction "2_2") (pintype "unspecified"))
      (node (ref "SW25") (pin "4") (pinfunction "GND-LED_4") (pintype "unspecified"))
    )
    (net (code "117") (name "Net-(SW26-GND-LED)") (class "Default")
      (node (ref "R26") (pin "2") (pinfunction "2_2") (pintype "unspecified"))
      (node (ref "SW26") (pin "4") (pinfunction "GND-LED_4") (pintype "unspecified"))
    )
    (net (code "118") (name "Net-(SW27-GND-LED)") (class "Default")
      (node (ref "R27") (pin "2") (pinfunction "2_2") (pintype "unspecified"))
      (node (ref "SW27") (pin "4") (pinfunction "GND-LED_4") (pintype "unspecified"))
    )
    (net (code "119") (name "Net-(SW28-GND-LED)") (class "Default")
      (node (ref "R28") (pin "2") (pinfunction "2_2") (pintype "unspecified"))
      (node (ref "SW28") (pin "4") (pinfunction "GND-LED_4") (pintype "unspecified"))
    )
    (net (code "120") (name "Net-(SW29-GND-LED)") (class "Default")
      (node (ref "R29") (pin "2") (pinfunction "2_2") (pintype "unspecified"))
      (node (ref "SW29") (pin "4") (pinfunction "GND-LED_4") (pintype "unspecified"))
    )
    (net (code "121") (name "Net-(SW30-GND-LED)") (class "Default")
      (node (ref "R30") (pin "2") (pinfunction "2_2") (pintype "unspecified"))
      (node (ref "SW30") (pin "4") (pinfunction "GND-LED_4") (pintype "unspecified"))
    )
    (net (code "122") (name "Net-(SW31-GND-LED)") (class "Default")
      (node (ref "R31") (pin "2") (pinfunction "2_2") (pintype "unspecified"))
      (node (ref "SW31") (pin "4") (pinfunction "GND-LED_4") (pintype "unspecified"))
      (node (ref "SW32") (pin "4") (pinfunction "GND-LED_4") (pintype "unspecified"))
    )
    (net (code "123") (name "Net-(SW33-GND-LED)") (class "Default")
      (node (ref "R32") (pin "2") (pinfunction "2_2") (pintype "unspecified"))
      (node (ref "SW33") (pin "4") (pinfunction "GND-LED_4") (pintype "unspecified"))
    )
    (net (code "124") (name "Net-(SW34-GND-LED)") (class "Default")
      (node (ref "R33") (pin "2") (pinfunction "2_2") (pintype "unspecified"))
      (node (ref "SW34") (pin "4") (pinfunction "GND-LED_4") (pintype "unspecified"))
    )
    (net (code "125") (name "Net-(SW35-GND-LED)") (class "Default")
      (node (ref "R34") (pin "2") (pinfunction "2_2") (pintype "unspecified"))
      (node (ref "SW35") (pin "4") (pinfunction "GND-LED_4") (pintype "unspecified"))
    )
    (net (code "126") (name "Net-(SW36-GND-LED)") (class "Default")
      (node (ref "R35") (pin "2") (pinfunction "2_2") (pintype "unspecified"))
      (node (ref "SW36") (pin "4") (pinfunction "GND-LED_4") (pintype "unspecified"))
      (node (ref "SW37") (pin "4") (pinfunction "GND-LED_4") (pintype "unspecified"))
    )
    (net (code "127") (name "Net-(SW38-GND-LED)") (class "Default")
      (node (ref "R36") (pin "2") (pinfunction "2_2") (pintype "unspecified"))
      (node (ref "SW38") (pin "4") (pinfunction "GND-LED_4") (pintype "unspecified"))
    )
    (net (code "128") (name "Net-(SW39-GND-LED)") (class "Default")
      (node (ref "R37") (pin "2") (pinfunction "2_2") (pintype "unspecified"))
      (node (ref "SW39") (pin "4") (pinfunction "GND-LED_4") (pintype "unspecified"))
    )
    (net (code "129") (name "Net-(SW40-GND-LED)") (class "Default")
      (node (ref "R38") (pin "2") (pinfunction "2_2") (pintype "unspecified"))
      (node (ref "SW40") (pin "4") (pinfunction "GND-LED_4") (pintype "unspecified"))
    )
    (net (code "130") (name "Net-(SW41-GND-LED)") (class "Default")
      (node (ref "R39") (pin "2") (pinfunction "2_2") (pintype "unspecified"))
      (node (ref "SW41") (pin "4") (pinfunction "GND-LED_4") (pintype "unspecified"))
    )
    (net (code "131") (name "Net-(SW42-GND-LED)") (class "Default")
      (node (ref "R40") (pin "2") (pinfunction "2_2") (pintype "unspecified"))
      (node (ref "SW42") (pin "4") (pinfunction "GND-LED_4") (pintype "unspecified"))
    )
    (net (code "132") (name "Net-(SW43-GND-LED)") (class "Default")
      (node (ref "R41") (pin "2") (pinfunction "2_2") (pintype "unspecified"))
      (node (ref "SW43") (pin "4") (pinfunction "GND-LED_4") (pintype "unspecified"))
    )
    (net (code "133") (name "Net-(SW44-GND-LED)") (class "Default")
      (node (ref "R42") (pin "2") (pinfunction "2_2") (pintype "unspecified"))
      (node (ref "SW44") (pin "4") (pinfunction "GND-LED_4") (pintype "unspecified"))
    )
    (net (code "134") (name "Net-(SW45-GND-LED)") (class "Default")
      (node (ref "R43") (pin "2") (pinfunction "2_2") (pintype "unspecified"))
      (node (ref "SW45") (pin "4") (pinfunction "GND-LED_4") (pintype "unspecified"))
    )
    (net (code "135") (name "Net-(SW46-GND-LED)") (class "Default")
      (node (ref "R44") (pin "2") (pinfunction "2_2") (pintype "unspecified"))
      (node (ref "SW46") (pin "4") (pinfunction "GND-LED_4") (pintype "unspecified"))
    )
    (net (code "136") (name "Net-(SW47-GND-LED)") (class "Default")
      (node (ref "R45") (pin "2") (pinfunction "2_2") (pintype "unspecified"))
      (node (ref "SW47") (pin "4") (pinfunction "GND-LED_4") (pintype "unspecified"))
    )
    (net (code "137") (name "Net-(SW48-GND-LED)") (class "Default")
      (node (ref "R46") (pin "2") (pinfunction "2_2") (pintype "unspecified"))
      (node (ref "SW48") (pin "4") (pinfunction "GND-LED_4") (pintype "unspecified"))
    )
    (net (code "138") (name "Net-(SW49-GND-LED)") (class "Default")
      (node (ref "R47") (pin "2") (pinfunction "2_2") (pintype "unspecified"))
      (node (ref "SW49") (pin "4") (pinfunction "GND-LED_4") (pintype "unspecified"))
    )
    (net (code "139") (name "Net-(SW50-GND-LED)") (class "Default")
      (node (ref "R48") (pin "2") (pinfunction "2_2") (pintype "unspecified"))
      (node (ref "SW50") (pin "4") (pinfunction "GND-LED_4") (pintype "unspecified"))
    )
    (net (code "140") (name "Net-(SW51-GND-LED)") (class "Default")
      (node (ref "R49") (pin "2") (pinfunction "2_2") (pintype "unspecified"))
      (node (ref "SW51") (pin "4") (pinfunction "GND-LED_4") (pintype "unspecified"))
    )
    (net (code "141") (name "Net-(SW52-GND-LED)") (class "Default")
      (node (ref "R50") (pin "2") (pinfunction "2_2") (pintype "unspecified"))
      (node (ref "SW52") (pin "4") (pinfunction "GND-LED_4") (pintype "unspecified"))
    )
    (net (code "142") (name "Net-(SW53-GND-LED)") (class "Default")
      (node (ref "R51") (pin "2") (pinfunction "2_2") (pintype "unspecified"))
      (node (ref "SW53") (pin "4") (pinfunction "GND-LED_4") (pintype "unspecified"))
    )
    (net (code "143") (name "Net-(SW54-GND-LED)") (class "Default")
      (node (ref "R52") (pin "2") (pinfunction "2_2") (pintype "unspecified"))
      (node (ref "SW54") (pin "4") (pinfunction "GND-LED_4") (pintype "unspecified"))
    )
    (net (code "144") (name "Net-(SW55-GND-LED)") (class "Default")
      (node (ref "R53") (pin "2") (pinfunction "2_2") (pintype "unspecified"))
      (node (ref "SW55") (pin "4") (pinfunction "GND-LED_4") (pintype "unspecified"))
    )
    (net (code "145") (name "Net-(SW56-GND-LED)") (class "Default")
      (node (ref "R54") (pin "2") (pinfunction "2_2") (pintype "unspecified"))
      (node (ref "SW56") (pin "4") (pinfunction "GND-LED_4") (pintype "unspecified"))
    )
    (net (code "146") (name "Net-(SW57-GND-LED)") (class "Default")
      (node (ref "R55") (pin "2") (pinfunction "2_2") (pintype "unspecified"))
      (node (ref "SW57") (pin "4") (pinfunction "GND-LED_4") (pintype "unspecified"))
    )
    (net (code "147") (name "Net-(SW58-GND-LED)") (class "Default")
      (node (ref "R56") (pin "2") (pinfunction "2_2") (pintype "unspecified"))
      (node (ref "SW58") (pin "4") (pinfunction "GND-LED_4") (pintype "unspecified"))
    )
    (net (code "148") (name "Net-(SW59-GND-LED)") (class "Default")
      (node (ref "R57") (pin "2") (pinfunction "2_2") (pintype "unspecified"))
      (node (ref "SW59") (pin "4") (pinfunction "GND-LED_4") (pintype "unspecified"))
    )
    (net (code "149") (name "Net-(SW60-GND-LED)") (class "Default")
      (node (ref "R58") (pin "2") (pinfunction "2_2") (pintype "unspecified"))
      (node (ref "SW60") (pin "4") (pinfunction "GND-LED_4") (pintype "unspecified"))
    )
    (net (code "150") (name "Net-(SW61-GND-LED)") (class "Default")
      (node (ref "R59") (pin "2") (pinfunction "2_2") (pintype "unspecified"))
      (node (ref "SW61") (pin "4") (pinfunction "GND-LED_4") (pintype "unspecified"))
    )
    (net (code "151") (name "Net-(SW62-GND-LED)") (class "Default")
      (node (ref "R60") (pin "2") (pinfunction "2_2") (pintype "unspecified"))
      (node (ref "SW62") (pin "4") (pinfunction "GND-LED_4") (pintype "unspecified"))
    )
    (net (code "152") (name "Net-(SW63-GND-LED)") (class "Default")
      (node (ref "R61") (pin "2") (pinfunction "2_2") (pintype "unspecified"))
      (node (ref "SW63") (pin "4") (pinfunction "GND-LED_4") (pintype "unspecified"))
    )
    (net (code "153") (name "Net-(SW64-GND-LED)") (class "Default")
      (node (ref "R62") (pin "2") (pinfunction "2_2") (pintype "unspecified"))
      (node (ref "SW64") (pin "4") (pinfunction "GND-LED_4") (pintype "unspecified"))
    )
    (net (code "154") (name "Net-(SW65-GND-LED)") (class "Default")
      (node (ref "R63") (pin "2") (pinfunction "2_2") (pintype "unspecified"))
      (node (ref "SW65") (pin "4") (pinfunction "GND-LED_4") (pintype "unspecified"))
    )
    (net (code "155") (name "Net-(SW66-GND-LED)") (class "Default")
      (node (ref "R64") (pin "2") (pinfunction "2_2") (pintype "unspecified"))
      (node (ref "SW66") (pin "4") (pinfunction "GND-LED_4") (pintype "unspecified"))
    )
    (net (code "156") (name "Net-(SW67-GND-LED)") (class "Default")
      (node (ref "R65") (pin "2") (pinfunction "2_2") (pintype "unspecified"))
      (node (ref "SW67") (pin "4") (pinfunction "GND-LED_4") (pintype "unspecified"))
    )
    (net (code "157") (name "Net-(SW68-GND-LED)") (class "Default")
      (node (ref "R66") (pin "2") (pinfunction "2_2") (pintype "unspecified"))
      (node (ref "SW68") (pin "4") (pinfunction "GND-LED_4") (pintype "unspecified"))
    )
    (net (code "158") (name "Net-(SW69-GND-LED)") (class "Default")
      (node (ref "R67") (pin "2") (pinfunction "2_2") (pintype "unspecified"))
      (node (ref "SW69") (pin "4") (pinfunction "GND-LED_4") (pintype "unspecified"))
    )
    (net (code "159") (name "Net-(SW70-GND-LED)") (class "Default")
      (node (ref "R68") (pin "2") (pinfunction "2_2") (pintype "unspecified"))
      (node (ref "SW70") (pin "4") (pinfunction "GND-LED_4") (pintype "unspecified"))
    )
    (net (code "160") (name "Net-(SW71-GND-LED)") (class "Default")
      (node (ref "R69") (pin "2") (pinfunction "2_2") (pintype "unspecified"))
      (node (ref "SW71") (pin "4") (pinfunction "GND-LED_4") (pintype "unspecified"))
    )
    (net (code "161") (name "Net-(U1-AREF)") (class "Default")
      (node (ref "C9") (pin "1") (pinfunction "1_1") (pintype "unspecified"))
      (node (ref "U1") (pin "42") (pinfunction "AREF_42") (pintype "unspecified"))
    )
    (net (code "162") (name "Net-(U1-D+)") (class "Default")
      (node (ref "R71") (pin "1") (pinfunction "1_1") (pintype "input"))
      (node (ref "U1") (pin "4") (pinfunction "D+_4") (pintype "unspecified"))
    )
    (net (code "163") (name "Net-(U1-D-)") (class "Default")
      (node (ref "R70") (pin "1") (pinfunction "1_1") (pintype "input"))
      (node (ref "U1") (pin "3") (pinfunction "D-_3") (pintype "unspecified"))
    )
    (net (code "164") (name "Net-(U1-PE2(HWB#))") (class "Default")
      (node (ref "R72") (pin "2") (pinfunction "2_2") (pintype "input"))
      (node (ref "U1") (pin "33") (pinfunction "PE2(HWB#)_33") (pintype "unspecified"))
    )
    (net (code "165") (name "Net-(U1-UCap)") (class "Default")
      (node (ref "C12") (pin "2") (pinfunction "2_2") (pintype "input"))
      (node (ref "U1") (pin "6") (pinfunction "UCap_6") (pintype "unspecified"))
    )
    (net (code "166") (name "Net-(U1-XTAL1)") (class "Default")
      (node (ref "C11") (pin "2") (pinfunction "2_2") (pintype "input"))
      (node (ref "U1") (pin "17") (pinfunction "XTAL1_17") (pintype "unspecified"))
      (node (ref "X1") (pin "1") (pinfunction "OSC1_1") (pintype "unspecified"))
    )
    (net (code "167") (name "Net-(U1-XTAL2)") (class "Default")
      (node (ref "C10") (pin "2") (pinfunction "2_2") (pintype "input"))
      (node (ref "U1") (pin "16") (pinfunction "XTAL2_16") (pintype "unspecified"))
      (node (ref "X1") (pin "3") (pinfunction "OSC2_3") (pintype "unspecified"))
    )
    (net (code "168") (name "Net-(USBC1-CC1)") (class "Default")
      (node (ref "R74") (pin "1") (pinfunction "1_1") (pintype "unspecified"))
      (node (ref "USBC1") (pin "A5") (pinfunction "CC1_A5") (pintype "unspecified"))
    )
    (net (code "169") (name "Net-(USBC1-CC2)") (class "Default")
      (node (ref "R75") (pin "2") (pinfunction "2_2") (pintype "unspecified"))
      (node (ref "USBC1") (pin "B5") (pinfunction "CC2_B5") (pintype "unspecified"))
    )
    (net (code "170") (name "Reset") (class "Default")
      (node (ref "BUTTON") (pin "1") (pinfunction "A_1") (pintype "unspecified"))
      (node (ref "BUTTON") (pin "2") (pinfunction "B_2") (pintype "unspecified"))
      (node (ref "R76") (pin "2") (pinfunction "2_2") (pintype "input"))
      (node (ref "U1") (pin "13") (pinfunction "RESET#_13") (pintype "unspecified"))
    )
    (net (code "171") (name "Row0") (class "Default")
      (node (ref "D1") (pin "1") (pinfunction "K_1") (pintype "unspecified"))
      (node (ref "D11") (pin "1") (pinfunction "K_1") (pintype "unspecified"))
      (node (ref "D16") (pin "1") (pinfunction "K_1") (pintype "unspecified"))
      (node (ref "D21") (pin "1") (pinfunction "K_1") (pintype "unspecified"))
      (node (ref "D26") (pin "1") (pinfunction "K_1") (pintype "unspecified"))
      (node (ref "D31") (pin "1") (pinfunction "K_1") (pintype "unspecified"))
      (node (ref "D36") (pin "1") (pinfunction "K_1") (pintype "unspecified"))
      (node (ref "D41") (pin "1") (pinfunction "K_1") (pintype "unspecified"))
      (node (ref "D46") (pin "1") (pinfunction "K_1") (pintype "unspecified"))
      (node (ref "D51") (pin "1") (pinfunction "K_1") (pintype "unspecified"))
      (node (ref "D56") (pin "1") (pinfunction "K_1") (pintype "unspecified"))
      (node (ref "D6") (pin "1") (pinfunction "K_1") (pintype "unspecified"))
      (node (ref "D61") (pin "1") (pinfunction "K_1") (pintype "unspecified"))
      (node (ref "D66") (pin "1") (pinfunction "K_1") (pintype "unspecified"))
      (node (ref "U1") (pin "8") (pinfunction "PB0(SS/PCINT0)_8") (pintype "unspecified"))
    )
    (net (code "172") (name "Row1") (class "Default")
      (node (ref "D12") (pin "1") (pinfunction "K_1") (pintype "unspecified"))
      (node (ref "D17") (pin "1") (pinfunction "K_1") (pintype "unspecified"))
      (node (ref "D2") (pin "1") (pinfunction "K_1") (pintype "unspecified"))
      (node (ref "D22") (pin "1") (pinfunction "K_1") (pintype "unspecified"))
      (node (ref "D27") (pin "1") (pinfunction "K_1") (pintype "unspecified"))
      (node (ref "D32") (pin "1") (pinfunction "K_1") (pintype "unspecified"))
      (node (ref "D37") (pin "1") (pinfunction "K_1") (pintype "unspecified"))
      (node (ref "D42") (pin "1") (pinfunction "K_1") (pintype "unspecified"))
      (node (ref "D47") (pin "1") (pinfunction "K_1") (pintype "unspecified"))
      (node (ref "D52") (pin "1") (pinfunction "K_1") (pintype "unspecified"))
      (node (ref "D57") (pin "1") (pinfunction "K_1") (pintype "unspecified"))
      (node (ref "D62") (pin "1") (pinfunction "K_1") (pintype "unspecified"))
      (node (ref "D67") (pin "1") (pinfunction "K_1") (pintype "unspecified"))
      (node (ref "D7") (pin "1") (pinfunction "K_1") (pintype "unspecified"))
      (node (ref "U1") (pin "9") (pinfunction "PB1(PCINT1/SCLK)_9") (pintype "unspecified"))
    )
    (net (code "173") (name "Row2") (class "Default")
      (node (ref "D13") (pin "1") (pinfunction "K_1") (pintype "unspecified"))
      (node (ref "D18") (pin "1") (pinfunction "K_1") (pintype "unspecified"))
      (node (ref "D23") (pin "1") (pinfunction "K_1") (pintype "unspecified"))
      (node (ref "D28") (pin "1") (pinfunction "K_1") (pintype "unspecified"))
      (node (ref "D3") (pin "1") (pinfunction "K_1") (pintype "unspecified"))
      (node (ref "D33") (pin "1") (pinfunction "K_1") (pintype "unspecified"))
      (node (ref "D38") (pin "1") (pinfunction "K_1") (pintype "unspecified"))
      (node (ref "D43") (pin "1") (pinfunction "K_1") (pintype "unspecified"))
      (node (ref "D48") (pin "1") (pinfunction "K_1") (pintype "unspecified"))
      (node (ref "D53") (pin "1") (pinfunction "K_1") (pintype "unspecified"))
      (node (ref "D58") (pin "1") (pinfunction "K_1") (pintype "unspecified"))
      (node (ref "D63") (pin "1") (pinfunction "K_1") (pintype "unspecified"))
      (node (ref "D68") (pin "1") (pinfunction "K_1") (pintype "unspecified"))
      (node (ref "D8") (pin "1") (pinfunction "K_1") (pintype "unspecified"))
      (node (ref "U1") (pin "10") (pinfunction "PB2(PDI/PCINT2/MOSI)_10") (pintype "unspecified"))
    )
    (net (code "174") (name "Row3") (class "Default")
      (node (ref "D14") (pin "1") (pinfunction "K_1") (pintype "unspecified"))
      (node (ref "D19") (pin "1") (pinfunction "K_1") (pintype "unspecified"))
      (node (ref "D24") (pin "1") (pinfunction "K_1") (pintype "unspecified"))
      (node (ref "D29") (pin "1") (pinfunction "K_1") (pintype "unspecified"))
      (node (ref "D34") (pin "1") (pinfunction "K_1") (pintype "unspecified"))
      (node (ref "D39") (pin "1") (pinfunction "K_1") (pintype "unspecified"))
      (node (ref "D4") (pin "1") (pinfunction "K_1") (pintype "unspecified"))
      (node (ref "D44") (pin "1") (pinfunction "K_1") (pintype "unspecified"))
      (node (ref "D49") (pin "1") (pinfunction "K_1") (pintype "unspecified"))
      (node (ref "D54") (pin "1") (pinfunction "K_1") (pintype "unspecified"))
      (node (ref "D59") (pin "1") (pinfunction "K_1") (pintype "unspecified"))
      (node (ref "D64") (pin "1") (pinfunction "K_1") (pintype "unspecified"))
      (node (ref "D69") (pin "1") (pinfunction "K_1") (pintype "unspecified"))
      (node (ref "D9") (pin "1") (pinfunction "K_1") (pintype "unspecified"))
      (node (ref "U1") (pin "11") (pinfunction "PB3(PDO/PCINT3/MISO)_11") (pintype "unspecified"))
    )
    (net (code "175") (name "Row4") (class "Default")
      (node (ref "D10") (pin "1") (pinfunction "K_1") (pintype "unspecified"))
      (node (ref "D15") (pin "1") (pinfunction "K_1") (pintype "unspecified"))
      (node (ref "D20") (pin "1") (pinfunction "K_1") (pintype "unspecified"))
      (node (ref "D25") (pin "1") (pinfunction "K_1") (pintype "unspecified"))
      (node (ref "D30") (pin "1") (pinfunction "K_1") (pintype "unspecified"))
      (node (ref "D35") (pin "1") (pinfunction "K_1") (pintype "unspecified"))
      (node (ref "D40") (pin "1") (pinfunction "K_1") (pintype "unspecified"))
      (node (ref "D45") (pin "1") (pinfunction "K_1") (pintype "unspecified"))
      (node (ref "D5") (pin "1") (pinfunction "K_1") (pintype "unspecified"))
      (node (ref "D50") (pin "1") (pinfunction "K_1") (pintype "unspecified"))
      (node (ref "D55") (pin "1") (pinfunction "K_1") (pintype "unspecified"))
      (node (ref "D60") (pin "1") (pinfunction "K_1") (pintype "unspecified"))
      (node (ref "D65") (pin "1") (pinfunction "K_1") (pintype "unspecified"))
      (node (ref "D70") (pin "1") (pinfunction "K_1") (pintype "unspecified"))
      (node (ref "U1") (pin "12") (pinfunction "PB7(PCINT7/OC0A/OC1C/RTS#)_12") (pintype "unspecified"))
    )
    (net (code "176") (name "SCL") (class "Default")
      (node (ref "OLED1") (pin "2") (pinfunction "SCL_2") (pintype "unspecified"))
      (node (ref "U1") (pin "18") (pinfunction "PD0(OC0B/SCL/INT0)_18") (pintype "unspecified"))
      (node (ref "U2") (pin "2") (pinfunction "._2") (pintype "unspecified"))
    )
    (net (code "177") (name "SDA") (class "Default")
      (node (ref "OLED1") (pin "1") (pinfunction "SDA_1") (pintype "unspecified"))
      (node (ref "U1") (pin "19") (pinfunction "PD1(SDA/INT1)_19") (pintype "unspecified"))
      (node (ref "U2") (pin "1") (pinfunction "._1") (pintype "unspecified"))
    )
    (net (code "178") (name "VCC") (class "Default")
      (node (ref "C3") (pin "2") (pinfunction "2_2") (pintype "unspecified"))
      (node (ref "C4") (pin "2") (pinfunction "2_2") (pintype "unspecified"))
      (node (ref "C5") (pin "2") (pinfunction "2_2") (pintype "unspecified"))
      (node (ref "C6") (pin "2") (pinfunction "2_2") (pintype "unspecified"))
      (node (ref "C7") (pin "2") (pinfunction "2_2") (pintype "input"))
      (node (ref "C8") (pin "2") (pinfunction "2_2") (pintype "unspecified"))
      (node (ref "DIP") (pin "4") (pinfunction "B1_4") (pintype "input"))
      (node (ref "ESD1") (pin "5") (pinfunction "VBUS_5") (pintype "unspecified"))
      (node (ref "OLED1") (pin "3") (pinfunction "Vcc_3") (pintype "unspecified"))
      (node (ref "PWR") (pin "1") (pinfunction "A_1") (pintype "unspecified"))
      (node (ref "R76") (pin "1") (pinfunction "1_1") (pintype "input"))
      (node (ref "U1") (pin "14") (pinfunction "VCC_14") (pintype "unspecified"))
      (node (ref "U1") (pin "2") (pinfunction "UVcc_2") (pintype "unspecified"))
      (node (ref "U1") (pin "24") (pinfunction "AVCC_24") (pintype "unspecified"))
      (node (ref "U1") (pin "34") (pinfunction "VCC_34") (pintype "unspecified"))
      (node (ref "U1") (pin "44") (pinfunction "AVCC_44") (pintype "unspecified"))
      (node (ref "U1") (pin "7") (pinfunction "VBus_7") (pintype "unspecified"))
      (node (ref "U2") (pin "3") (pinfunction "._3") (pintype "unspecified"))
      (node (ref "USBC1") (pin "A4") (pinfunction "VBUS_A4") (pintype "unspecified"))
      (node (ref "USBC1") (pin "A9") (pinfunction "VBUS_A9") (pintype "unspecified"))
    )
    (net (code "179") (name "en1_A") (class "Default")
      (node (ref "C2") (pin "2") (pinfunction "2_2") (pintype "unspecified"))
      (node (ref "ENC1") (pin "A") (pinfunction "A_A") (pintype "unspecified"))
      (node (ref "U1") (pin "25") (pinfunction "PD4(ICP1/ADC8)_25") (pintype "unspecified"))
    )
    (net (code "180") (name "en1_B") (class "Default")
      (node (ref "C1") (pin "1") (pinfunction "1_1") (pintype "unspecified"))
      (node (ref "ENC1") (pin "B") (pinfunction "B_B") (pintype "unspecified"))
      (node (ref "U1") (pin "26") (pinfunction "PD6(T1/OC4D#/ADC9)_26") (pintype "unspecified"))
    )
    (net (code "181") (name "gpio1") (class "Default")
      (node (ref "DIP") (pin "3") (pinfunction "B2_3") (pintype "input"))
      (node (ref "U1") (pin "41") (pinfunction "PF0(ADC0)_41") (pintype "unspecified"))
    )
    (net (code "182") (name "unconnected-(ENC1-Pad6)") (class "Default")
      (node (ref "ENC1") (pin "6") (pinfunction "6_6") (pintype "unspecified+no_connect"))
    )
    (net (code "183") (name "unconnected-(ENC1-Pad7)") (class "Default")
      (node (ref "ENC1") (pin "7") (pinfunction "7_7") (pintype "unspecified+no_connect"))
    )
    (net (code "184") (name "unconnected-(U1-PE6(INT.6{slash}AIN0)-Pad1)") (class "Default")
      (node (ref "U1") (pin "1") (pinfunction "PE6(INT.6/AIN0)_1") (pintype "unspecified+no_connect"))
    )
    (net (code "185") (name "unconnected-(USBC1-Pad0)") (class "Default")
      (node (ref "USBC1") (pin "0") (pinfunction "0_0") (pintype "unspecified+no_connect"))
    )
    (net (code "186") (name "unconnected-(USBC1-Pad0)_1") (class "Default")
      (node (ref "USBC1") (pin "0") (pinfunction "0_0") (pintype "unspecified+no_connect"))
    )
    (net (code "187") (name "unconnected-(USBC1-Pad0)_2") (class "Default")
      (node (ref "USBC1") (pin "0") (pinfunction "0_0") (pintype "unspecified+no_connect"))
    )
    (net (code "188") (name "unconnected-(USBC1-Pad0)_3") (class "Default")
      (node (ref "USBC1") (pin "0") (pinfunction "0_0") (pintype "unspecified+no_connect"))
    )
    (net (code "189") (name "unconnected-(USBC1-SBU1-PadA8)") (class "Default")
      (node (ref "USBC1") (pin "A8") (pinfunction "SBU1_A8") (pintype "unspecified+no_connect"))
    )
    (net (code "190") (name "unconnected-(USBC1-SBU2-PadB8)") (class "Default")
      (node (ref "USBC1") (pin "B8") (pinfunction "SBU2_B8") (pintype "unspecified+no_connect"))
    )
  )
)
